# io-board-c-4.net
KiCad netlist of a schematic drawn in EAGLE
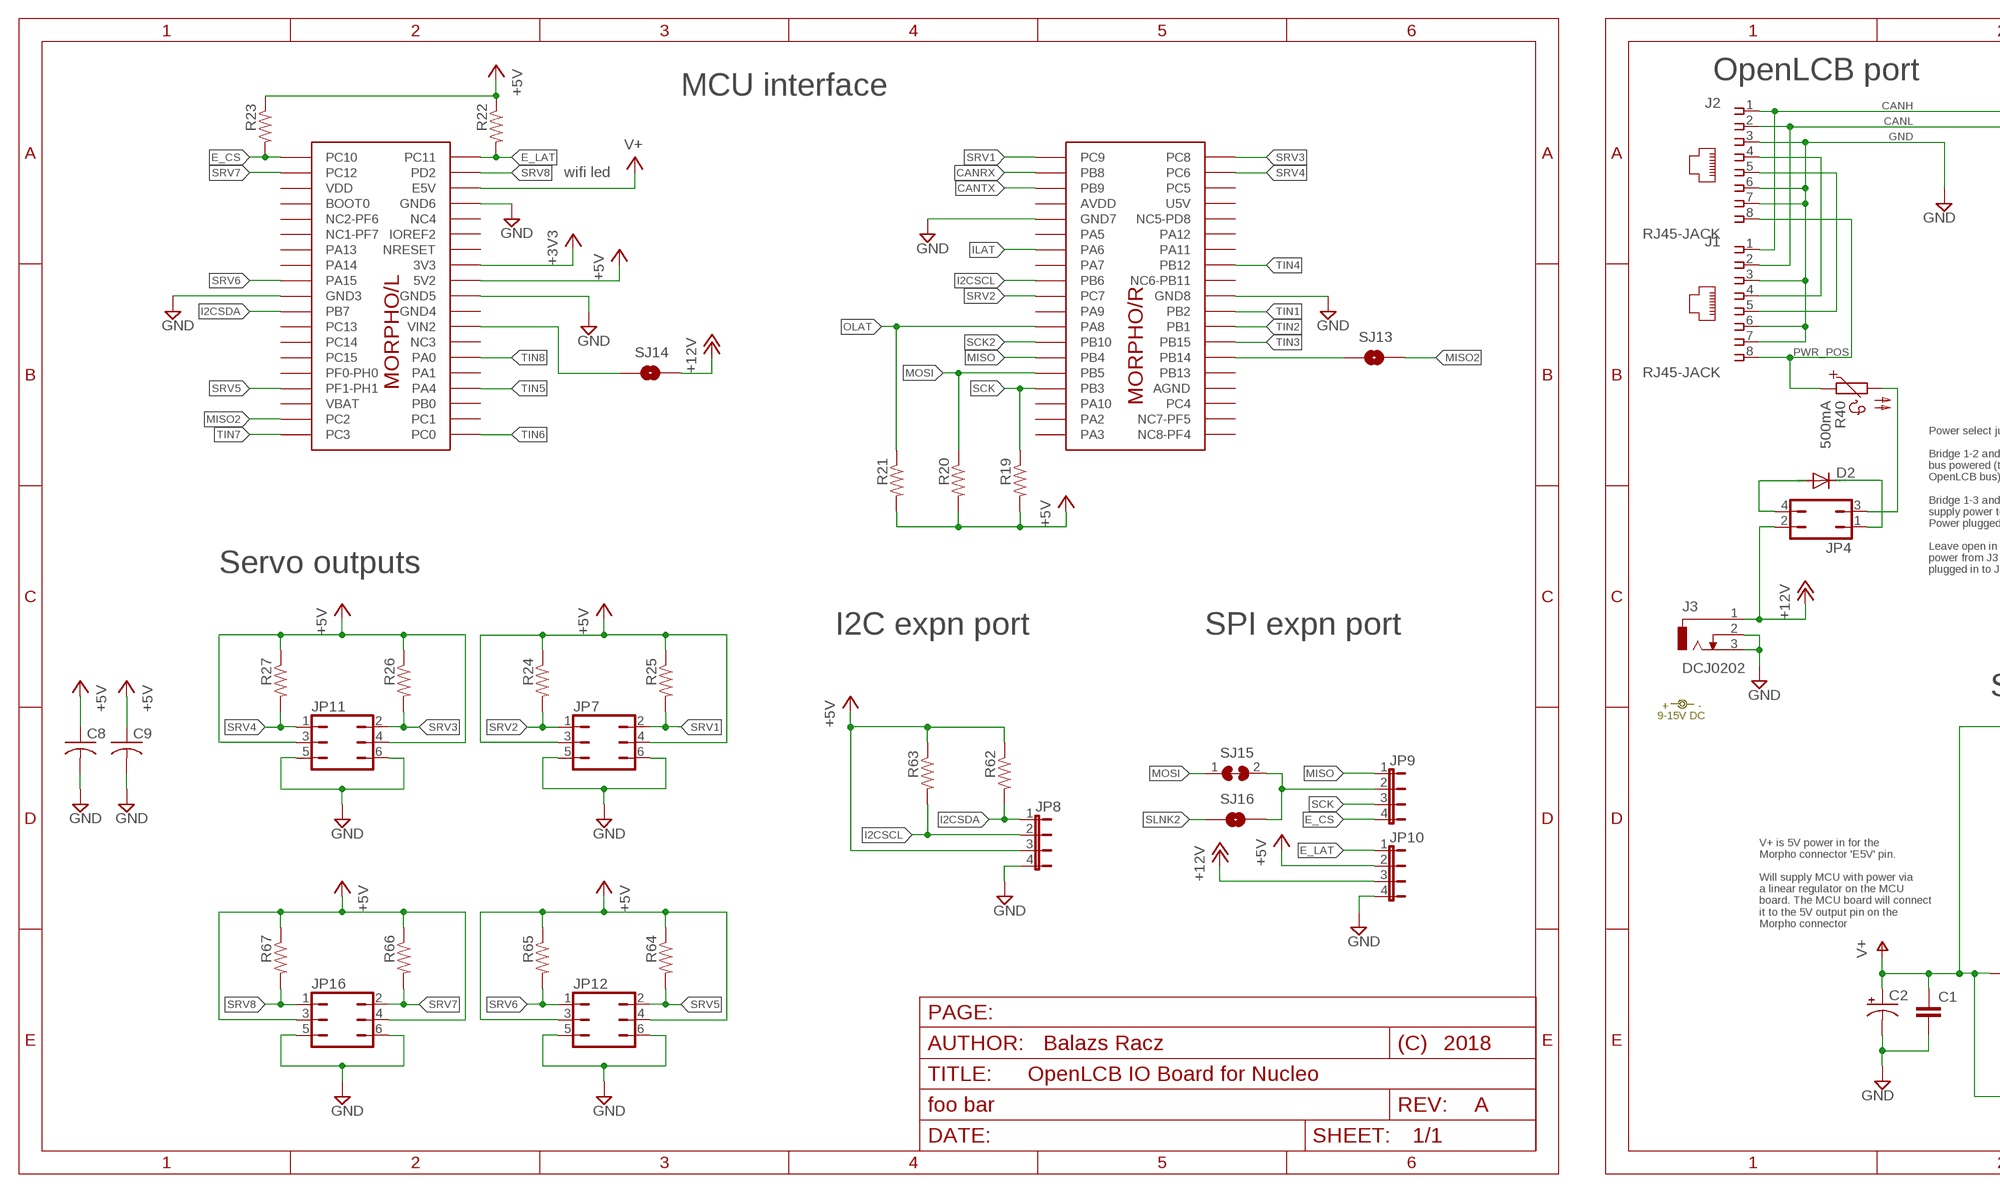
[diagram p0: schematic, sheet 1, part 1 of 3]
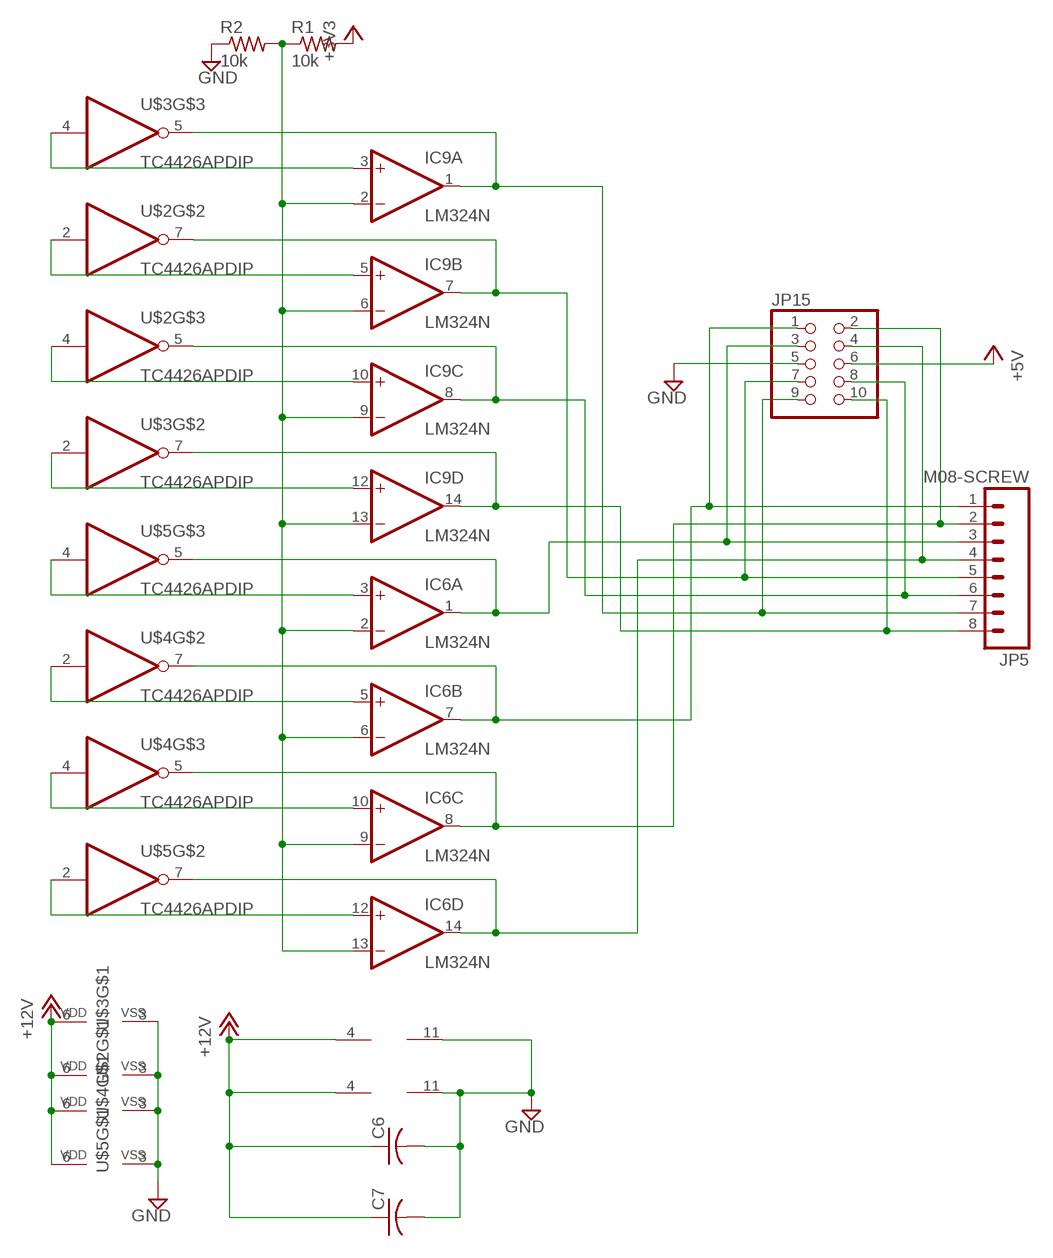
[diagram p1: schematic, sheet 1, part 2 of 3]
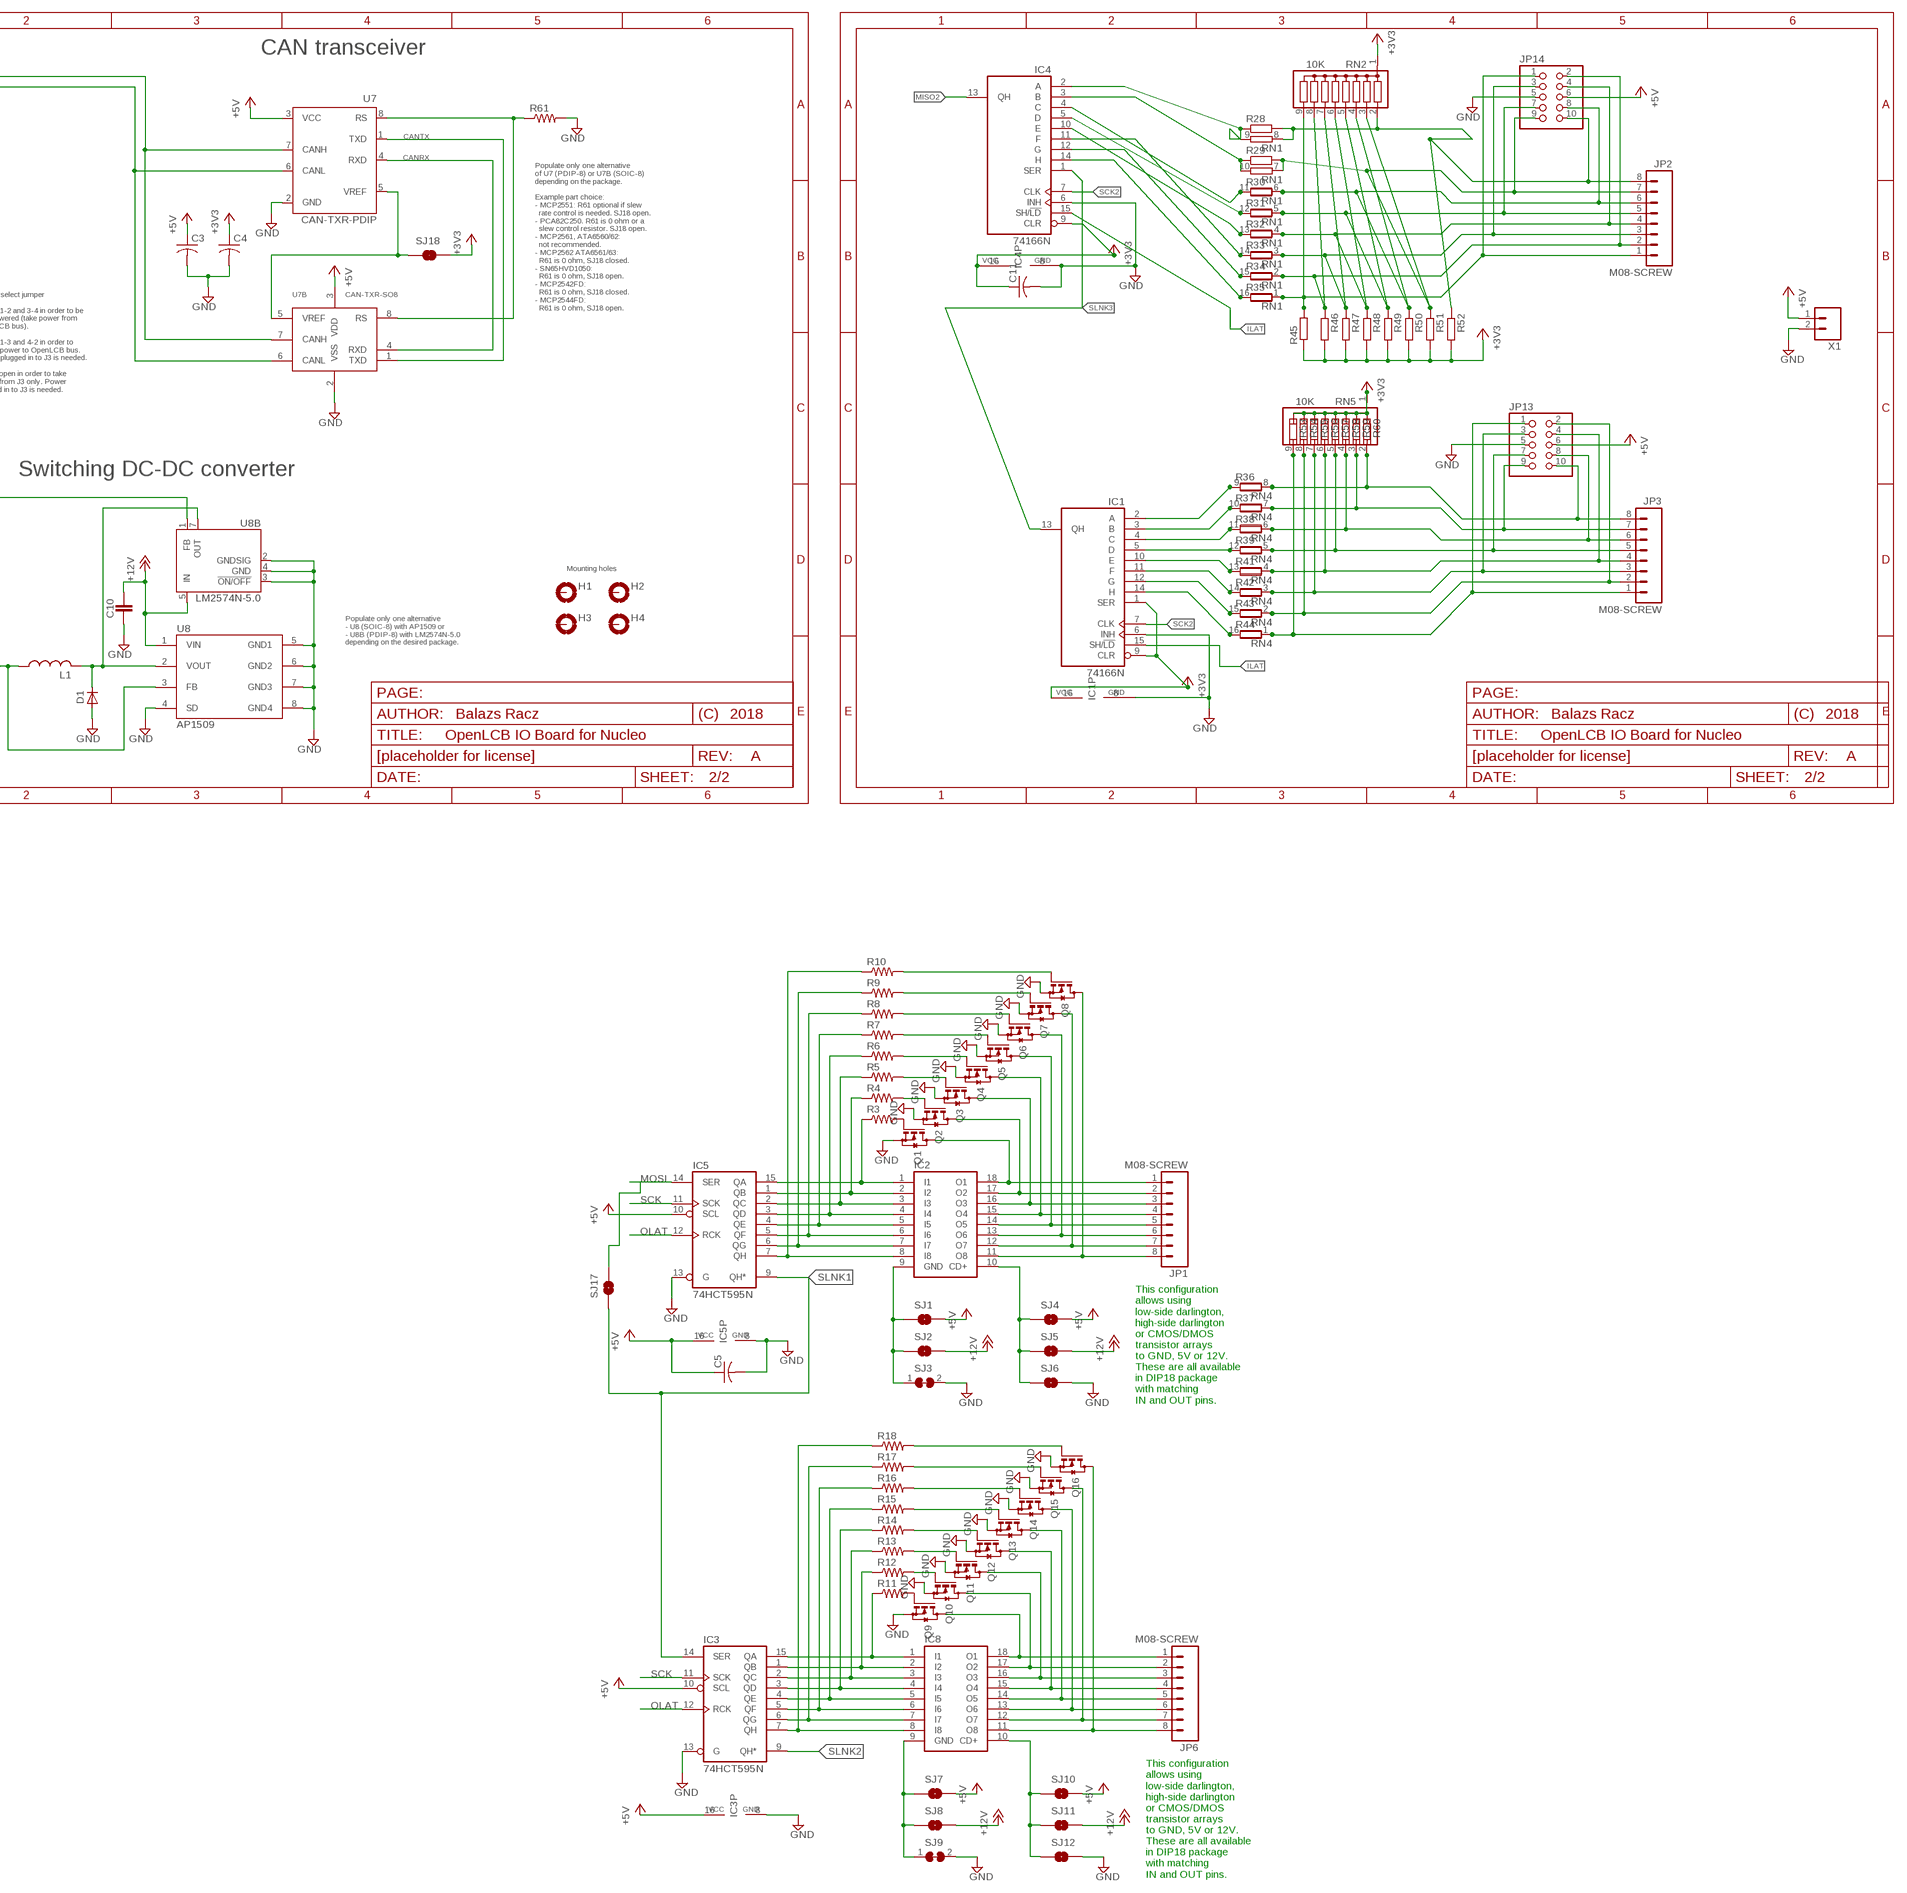
[diagram p2: schematic, sheet 1, part 3 of 3]

(export (version "E")
  (design (tool "Eeschema 10.0.6"))
  (components
    (comp (ref "+12V")
      (value "9-15V DC")
      (footprint "eagle-import:POWER_USAGE")
      (libsource (lib "eagle-import") (part "DOC-POWER_LABEL"))
    )
    (comp (ref "C1")
      (value "C-EUC1206")
      (footprint "eagle-import:C1206")
      (libsource (lib "eagle-import") (part "C-EUC1206"))
    )
    (comp (ref "C2")
      (value "CPOL-USE2.5-5")
      (footprint "eagle-import:E2,5-5")
      (libsource (lib "eagle-import") (part "CPOL-USE2.5-5"))
    )
    (comp (ref "C3")
      (value "C-USC0805")
      (footprint "eagle-import:C0805")
      (libsource (lib "eagle-import") (part "C-USC0805"))
    )
    (comp (ref "C4")
      (value "C-USC0805")
      (footprint "eagle-import:C0805")
      (libsource (lib "eagle-import") (part "C-USC0805"))
    )
    (comp (ref "C5")
      (value "C-USC0805")
      (footprint "eagle-import:C0805")
      (libsource (lib "eagle-import") (part "C-USC0805"))
    )
    (comp (ref "C6")
      (value "C-USC1206")
      (footprint "eagle-import:C1206")
      (libsource (lib "eagle-import") (part "C-USC1206"))
    )
    (comp (ref "C7")
      (value "C-USC1206")
      (footprint "eagle-import:C1206")
      (libsource (lib "eagle-import") (part "C-USC1206"))
    )
    (comp (ref "C8")
      (value "C-USC1206")
      (footprint "eagle-import:C1206")
      (libsource (lib "eagle-import") (part "C-USC1206"))
    )
    (comp (ref "C9")
      (value "C-USC1206")
      (footprint "eagle-import:C1206")
      (libsource (lib "eagle-import") (part "C-USC1206"))
    )
    (comp (ref "C10")
      (value "C-EUC1206")
      (footprint "eagle-import:C1206")
      (libsource (lib "eagle-import") (part "C-EUC1206"))
    )
    (comp (ref "C11")
      (value "C-USC0805")
      (footprint "eagle-import:C0805")
      (libsource (lib "eagle-import") (part "C-USC0805"))
    )
    (comp (ref "D1")
      (value "DIODE-DO41-7.6")
      (footprint "eagle-import:DO41-7.6")
      (libsource (lib "eagle-import") (part "DIODE-DO41-7.6"))
    )
    (comp (ref "D2")
      (value "DIODE-DO41-7.6")
      (footprint "eagle-import:DO41-7.6")
      (libsource (lib "eagle-import") (part "DIODE-DO41-7.6"))
    )
    (comp (ref "H1")
      (value "MOUNT-PAD-ROUND3.3")
      (footprint "eagle-import:3,3-PAD")
      (libsource (lib "eagle-import") (part "MOUNT-PAD-ROUND3.3"))
    )
    (comp (ref "H2")
      (value "MOUNT-PAD-ROUND3.3")
      (footprint "eagle-import:3,3-PAD")
      (libsource (lib "eagle-import") (part "MOUNT-PAD-ROUND3.3"))
    )
    (comp (ref "H3")
      (value "MOUNT-PAD-ROUND3.3")
      (footprint "eagle-import:3,3-PAD")
      (libsource (lib "eagle-import") (part "MOUNT-PAD-ROUND3.3"))
    )
    (comp (ref "H4")
      (value "MOUNT-PAD-ROUND3.3")
      (footprint "eagle-import:3,3-PAD")
      (libsource (lib "eagle-import") (part "MOUNT-PAD-ROUND3.3"))
    )
    (comp (ref "IC1")
      (value "74166N")
      (footprint "eagle-import:DIL16")
      (libsource (lib "eagle-import") (part "74166N"))
    )
    (comp (ref "IC2")
      (value "ULN2803A")
      (footprint "eagle-import:DIL18-THIN")
      (libsource (lib "eagle-import") (part "ULN2803A"))
    )
    (comp (ref "IC3")
      (value "74HCT595N")
      (footprint "eagle-import:DIL16")
      (libsource (lib "eagle-import") (part "74595NHCT"))
    )
    (comp (ref "IC4")
      (value "74166N")
      (footprint "eagle-import:DIL16")
      (libsource (lib "eagle-import") (part "74166N"))
    )
    (comp (ref "IC5")
      (value "74HCT595N")
      (footprint "eagle-import:DIL16")
      (libsource (lib "eagle-import") (part "74595NHCT"))
    )
    (comp (ref "IC6")
      (value "LM324N")
      (footprint "eagle-import:DIL14")
      (libsource (lib "eagle-import") (part "LM324N"))
    )
    (comp (ref "IC8")
      (value "ULN2803A")
      (footprint "eagle-import:DIL18-THIN")
      (libsource (lib "eagle-import") (part "ULN2803A"))
    )
    (comp (ref "IC9")
      (value "LM324N")
      (footprint "eagle-import:DIL14")
      (libsource (lib "eagle-import") (part "LM324N"))
    )
    (comp (ref "J1")
      (value "RJ45-JACK")
      (footprint "eagle-import:RJ45-PULSE-E5J88")
      (libsource (lib "eagle-import") (part "RJ45-JACKRJ45-PULSE-E5J00"))
    )
    (comp (ref "J2")
      (value "RJ45-JACK")
      (footprint "eagle-import:RJ45-PULSE-E5J88")
      (libsource (lib "eagle-import") (part "RJ45-JACKRJ45-PULSE-E5J00"))
    )
    (comp (ref "J3")
      (value "DCJ0202")
      (footprint "eagle-import:DCJ0202")
      (libsource (lib "eagle-import") (part "DCJ0202"))
    )
    (comp (ref "JP1")
      (value "M08-SCREW")
      (footprint "eagle-import:1X08_TERMINAL")
      (libsource (lib "eagle-import") (part "M08-SCREW"))
    )
    (comp (ref "JP2")
      (value "M08-SCREW")
      (footprint "eagle-import:1X08_TERMINAL")
      (libsource (lib "eagle-import") (part "M08-SCREW"))
    )
    (comp (ref "JP3")
      (value "M08-SCREW")
      (footprint "eagle-import:1X08_TERMINAL")
      (libsource (lib "eagle-import") (part "M08-SCREW"))
    )
    (comp (ref "JP4")
      (value "JP2Q")
      (footprint "eagle-import:JP2Q")
      (libsource (lib "eagle-import") (part "JP2Q"))
    )
    (comp (ref "JP5")
      (value "M08-SCREW")
      (footprint "eagle-import:1X08_TERMINAL")
      (libsource (lib "eagle-import") (part "M08-SCREW"))
    )
    (comp (ref "JP6")
      (value "M08-SCREW")
      (footprint "eagle-import:1X08_TERMINAL")
      (libsource (lib "eagle-import") (part "M08-SCREW"))
    )
    (comp (ref "JP7")
      (value "JP3Q")
      (footprint "eagle-import:JP3Q")
      (libsource (lib "eagle-import") (part "JP3Q"))
    )
    (comp (ref "JP8")
      (value "JP4-FLAT")
      (footprint "eagle-import:JP4F")
      (libsource (lib "eagle-import") (part "JP4-FLAT"))
    )
    (comp (ref "JP9")
      (value "JP4-FLAT")
      (footprint "eagle-import:JP4F")
      (libsource (lib "eagle-import") (part "JP4-FLAT"))
    )
    (comp (ref "JP10")
      (value "JP4-FLAT")
      (footprint "eagle-import:JP4F")
      (libsource (lib "eagle-import") (part "JP4-FLAT"))
    )
    (comp (ref "JP11")
      (value "JP3Q")
      (footprint "eagle-import:JP3Q")
      (libsource (lib "eagle-import") (part "JP3Q"))
    )
    (comp (ref "JP12")
      (value "JP3Q")
      (footprint "eagle-import:JP3Q")
      (libsource (lib "eagle-import") (part "JP3Q"))
    )
    (comp (ref "JP13")
      (value "PINHD-2X5CN")
      (footprint "eagle-import:CON10M")
      (libsource (lib "eagle-import") (part "PINHD-2X5CN"))
    )
    (comp (ref "JP14")
      (value "PINHD-2X5CN")
      (footprint "eagle-import:CON10M")
      (libsource (lib "eagle-import") (part "PINHD-2X5CN"))
    )
    (comp (ref "JP15")
      (value "PINHD-2X5CN")
      (footprint "eagle-import:CON10M")
      (libsource (lib "eagle-import") (part "PINHD-2X5CN"))
    )
    (comp (ref "JP16")
      (value "JP3Q")
      (footprint "eagle-import:JP3Q")
      (libsource (lib "eagle-import") (part "JP3Q"))
    )
    (comp (ref "L1")
      (value "L-US")
      (footprint "eagle-import:L5-8,5")
      (libsource (lib "eagle-import") (part "L-US"))
    )
    (comp (ref "Q1")
      (value "BSS123")
      (footprint "eagle-import:SOT23")
      (libsource (lib "eagle-import") (part "BSS123"))
    )
    (comp (ref "Q2")
      (value "BSS123")
      (footprint "eagle-import:SOT23")
      (libsource (lib "eagle-import") (part "BSS123"))
    )
    (comp (ref "Q3")
      (value "BSS123")
      (footprint "eagle-import:SOT23")
      (libsource (lib "eagle-import") (part "BSS123"))
    )
    (comp (ref "Q4")
      (value "BSS123")
      (footprint "eagle-import:SOT23")
      (libsource (lib "eagle-import") (part "BSS123"))
    )
    (comp (ref "Q5")
      (value "BSS123")
      (footprint "eagle-import:SOT23")
      (libsource (lib "eagle-import") (part "BSS123"))
    )
    (comp (ref "Q6")
      (value "BSS123")
      (footprint "eagle-import:SOT23")
      (libsource (lib "eagle-import") (part "BSS123"))
    )
    (comp (ref "Q7")
      (value "BSS123")
      (footprint "eagle-import:SOT23")
      (libsource (lib "eagle-import") (part "BSS123"))
    )
    (comp (ref "Q8")
      (value "BSS123")
      (footprint "eagle-import:SOT23")
      (libsource (lib "eagle-import") (part "BSS123"))
    )
    (comp (ref "Q9")
      (value "BSS123")
      (footprint "eagle-import:SOT23")
      (libsource (lib "eagle-import") (part "BSS123"))
    )
    (comp (ref "Q10")
      (value "BSS123")
      (footprint "eagle-import:SOT23")
      (libsource (lib "eagle-import") (part "BSS123"))
    )
    (comp (ref "Q11")
      (value "BSS123")
      (footprint "eagle-import:SOT23")
      (libsource (lib "eagle-import") (part "BSS123"))
    )
    (comp (ref "Q12")
      (value "BSS123")
      (footprint "eagle-import:SOT23")
      (libsource (lib "eagle-import") (part "BSS123"))
    )
    (comp (ref "Q13")
      (value "BSS123")
      (footprint "eagle-import:SOT23")
      (libsource (lib "eagle-import") (part "BSS123"))
    )
    (comp (ref "Q14")
      (value "BSS123")
      (footprint "eagle-import:SOT23")
      (libsource (lib "eagle-import") (part "BSS123"))
    )
    (comp (ref "Q15")
      (value "BSS123")
      (footprint "eagle-import:SOT23")
      (libsource (lib "eagle-import") (part "BSS123"))
    )
    (comp (ref "Q16")
      (value "BSS123")
      (footprint "eagle-import:SOT23")
      (libsource (lib "eagle-import") (part "BSS123"))
    )
    (comp (ref "R1")
      (value "10k")
      (footprint "eagle-import:R0805")
      (libsource (lib "eagle-import") (part "R-US_R0805"))
    )
    (comp (ref "R2")
      (value "10k")
      (footprint "eagle-import:R0805")
      (libsource (lib "eagle-import") (part "R-US_R0805"))
    )
    (comp (ref "R3")
      (value "R-US_R0603")
      (footprint "eagle-import:R0603")
      (libsource (lib "eagle-import") (part "R-US_R0603"))
    )
    (comp (ref "R4")
      (value "R-US_R0603")
      (footprint "eagle-import:R0603")
      (libsource (lib "eagle-import") (part "R-US_R0603"))
    )
    (comp (ref "R5")
      (value "R-US_R0603")
      (footprint "eagle-import:R0603")
      (libsource (lib "eagle-import") (part "R-US_R0603"))
    )
    (comp (ref "R6")
      (value "R-US_R0603")
      (footprint "eagle-import:R0603")
      (libsource (lib "eagle-import") (part "R-US_R0603"))
    )
    (comp (ref "R7")
      (value "R-US_R0603")
      (footprint "eagle-import:R0603")
      (libsource (lib "eagle-import") (part "R-US_R0603"))
    )
    (comp (ref "R8")
      (value "R-US_R0603")
      (footprint "eagle-import:R0603")
      (libsource (lib "eagle-import") (part "R-US_R0603"))
    )
    (comp (ref "R9")
      (value "R-US_R0603")
      (footprint "eagle-import:R0603")
      (libsource (lib "eagle-import") (part "R-US_R0603"))
    )
    (comp (ref "R10")
      (value "R-US_R0603")
      (footprint "eagle-import:R0603")
      (libsource (lib "eagle-import") (part "R-US_R0603"))
    )
    (comp (ref "R11")
      (value "R-US_R0603")
      (footprint "eagle-import:R0603")
      (libsource (lib "eagle-import") (part "R-US_R0603"))
    )
    (comp (ref "R12")
      (value "R-US_R0603")
      (footprint "eagle-import:R0603")
      (libsource (lib "eagle-import") (part "R-US_R0603"))
    )
    (comp (ref "R13")
      (value "R-US_R0603")
      (footprint "eagle-import:R0603")
      (libsource (lib "eagle-import") (part "R-US_R0603"))
    )
    (comp (ref "R14")
      (value "R-US_R0603")
      (footprint "eagle-import:R0603")
      (libsource (lib "eagle-import") (part "R-US_R0603"))
    )
    (comp (ref "R15")
      (value "R-US_R0603")
      (footprint "eagle-import:R0603")
      (libsource (lib "eagle-import") (part "R-US_R0603"))
    )
    (comp (ref "R16")
      (value "R-US_R0603")
      (footprint "eagle-import:R0603")
      (libsource (lib "eagle-import") (part "R-US_R0603"))
    )
    (comp (ref "R17")
      (value "R-US_R0603")
      (footprint "eagle-import:R0603")
      (libsource (lib "eagle-import") (part "R-US_R0603"))
    )
    (comp (ref "R18")
      (value "R-US_R0603")
      (footprint "eagle-import:R0603")
      (libsource (lib "eagle-import") (part "R-US_R0603"))
    )
    (comp (ref "R19")
      (value "R-US_R0805")
      (footprint "eagle-import:R0805")
      (libsource (lib "eagle-import") (part "rcl_334_R-US_R0805"))
    )
    (comp (ref "R20")
      (value "R-US_R0805")
      (footprint "eagle-import:R0805")
      (libsource (lib "eagle-import") (part "rcl_334_R-US_R0805"))
    )
    (comp (ref "R21")
      (value "R-US_R0805")
      (footprint "eagle-import:R0805")
      (libsource (lib "eagle-import") (part "rcl_334_R-US_R0805"))
    )
    (comp (ref "R22")
      (value "R-US_R0805")
      (footprint "eagle-import:R0805")
      (libsource (lib "eagle-import") (part "rcl_334_R-US_R0805"))
    )
    (comp (ref "R23")
      (value "R-US_R0805")
      (footprint "eagle-import:R0805")
      (libsource (lib "eagle-import") (part "rcl_334_R-US_R0805"))
    )
    (comp (ref "R24")
      (value "R-US_R0805")
      (footprint "eagle-import:R0805")
      (libsource (lib "eagle-import") (part "rcl_334_R-US_R0805"))
    )
    (comp (ref "R25")
      (value "R-US_R0805")
      (footprint "eagle-import:R0805")
      (libsource (lib "eagle-import") (part "rcl_334_R-US_R0805"))
    )
    (comp (ref "R26")
      (value "R-US_R0805")
      (footprint "eagle-import:R0805")
      (libsource (lib "eagle-import") (part "rcl_334_R-US_R0805"))
    )
    (comp (ref "R27")
      (value "R-US_R0805")
      (footprint "eagle-import:R0805")
      (libsource (lib "eagle-import") (part "rcl_334_R-US_R0805"))
    )
    (comp (ref "R28")
      (value "R-EU_R0603")
      (footprint "eagle-import:R0603")
      (libsource (lib "eagle-import") (part "R-EU_R0603"))
    )
    (comp (ref "R29")
      (value "R-EU_R0603")
      (footprint "eagle-import:R0603")
      (libsource (lib "eagle-import") (part "R-EU_R0603"))
    )
    (comp (ref "R30")
      (value "R-EU_R0603")
      (footprint "eagle-import:R0603")
      (libsource (lib "eagle-import") (part "R-EU_R0603"))
    )
    (comp (ref "R31")
      (value "R-EU_R0603")
      (footprint "eagle-import:R0603")
      (libsource (lib "eagle-import") (part "R-EU_R0603"))
    )
    (comp (ref "R32")
      (value "R-EU_R0603")
      (footprint "eagle-import:R0603")
      (libsource (lib "eagle-import") (part "R-EU_R0603"))
    )
    (comp (ref "R33")
      (value "R-EU_R0603")
      (footprint "eagle-import:R0603")
      (libsource (lib "eagle-import") (part "R-EU_R0603"))
    )
    (comp (ref "R34")
      (value "R-EU_R0603")
      (footprint "eagle-import:R0603")
      (libsource (lib "eagle-import") (part "R-EU_R0603"))
    )
    (comp (ref "R35")
      (value "R-EU_R0603")
      (footprint "eagle-import:R0603")
      (libsource (lib "eagle-import") (part "R-EU_R0603"))
    )
    (comp (ref "R36")
      (value "R-EU_R0603")
      (footprint "eagle-import:R0603")
      (libsource (lib "eagle-import") (part "R-EU_R0603"))
    )
    (comp (ref "R37")
      (value "R-EU_R0603")
      (footprint "eagle-import:R0603")
      (libsource (lib "eagle-import") (part "R-EU_R0603"))
    )
    (comp (ref "R38")
      (value "R-EU_R0603")
      (footprint "eagle-import:R0603")
      (libsource (lib "eagle-import") (part "R-EU_R0603"))
    )
    (comp (ref "R39")
      (value "R-EU_R0603")
      (footprint "eagle-import:R0603")
      (libsource (lib "eagle-import") (part "R-EU_R0603"))
    )
    (comp (ref "R40")
      (value "500mA")
      (footprint "eagle-import:PTC1812")
      (libsource (lib "eagle-import") (part "PTC_1812"))
    )
    (comp (ref "R41")
      (value "R-EU_R0603")
      (footprint "eagle-import:R0603")
      (libsource (lib "eagle-import") (part "R-EU_R0603"))
    )
    (comp (ref "R42")
      (value "R-EU_R0603")
      (footprint "eagle-import:R0603")
      (libsource (lib "eagle-import") (part "R-EU_R0603"))
    )
    (comp (ref "R43")
      (value "R-EU_R0603")
      (footprint "eagle-import:R0603")
      (libsource (lib "eagle-import") (part "R-EU_R0603"))
    )
    (comp (ref "R44")
      (value "R-EU_R0603")
      (footprint "eagle-import:R0603")
      (libsource (lib "eagle-import") (part "R-EU_R0603"))
    )
    (comp (ref "R45")
      (value "R-EU_R0603")
      (footprint "eagle-import:R0603")
      (libsource (lib "eagle-import") (part "R-EU_R0603"))
    )
    (comp (ref "R46")
      (value "R-EU_R0603")
      (footprint "eagle-import:R0603")
      (libsource (lib "eagle-import") (part "R-EU_R0603"))
    )
    (comp (ref "R47")
      (value "R-EU_R0603")
      (footprint "eagle-import:R0603")
      (libsource (lib "eagle-import") (part "R-EU_R0603"))
    )
    (comp (ref "R48")
      (value "R-EU_R0603")
      (footprint "eagle-import:R0603")
      (libsource (lib "eagle-import") (part "R-EU_R0603"))
    )
    (comp (ref "R49")
      (value "R-EU_R0603")
      (footprint "eagle-import:R0603")
      (libsource (lib "eagle-import") (part "R-EU_R0603"))
    )
    (comp (ref "R50")
      (value "R-EU_R0603")
      (footprint "eagle-import:R0603")
      (libsource (lib "eagle-import") (part "R-EU_R0603"))
    )
    (comp (ref "R51")
      (value "R-EU_R0603")
      (footprint "eagle-import:R0603")
      (libsource (lib "eagle-import") (part "R-EU_R0603"))
    )
    (comp (ref "R52")
      (value "R-EU_R0603")
      (footprint "eagle-import:R0603")
      (libsource (lib "eagle-import") (part "R-EU_R0603"))
    )
    (comp (ref "R53")
      (value "R-EU_R0603")
      (footprint "eagle-import:R0603")
      (libsource (lib "eagle-import") (part "R-EU_R0603"))
    )
    (comp (ref "R54")
      (value "R-EU_R0603")
      (footprint "eagle-import:R0603")
      (libsource (lib "eagle-import") (part "R-EU_R0603"))
    )
    (comp (ref "R55")
      (value "R-EU_R0603")
      (footprint "eagle-import:R0603")
      (libsource (lib "eagle-import") (part "R-EU_R0603"))
    )
    (comp (ref "R56")
      (value "R-EU_R0603")
      (footprint "eagle-import:R0603")
      (libsource (lib "eagle-import") (part "R-EU_R0603"))
    )
    (comp (ref "R57")
      (value "R-EU_R0603")
      (footprint "eagle-import:R0603")
      (libsource (lib "eagle-import") (part "R-EU_R0603"))
    )
    (comp (ref "R58")
      (value "R-EU_R0603")
      (footprint "eagle-import:R0603")
      (libsource (lib "eagle-import") (part "R-EU_R0603"))
    )
    (comp (ref "R59")
      (value "R-EU_R0603")
      (footprint "eagle-import:R0603")
      (libsource (lib "eagle-import") (part "R-EU_R0603"))
    )
    (comp (ref "R60")
      (value "R-EU_R0603")
      (footprint "eagle-import:R0603")
      (libsource (lib "eagle-import") (part "R-EU_R0603"))
    )
    (comp (ref "R61")
      (value "R-US_R0805")
      (footprint "eagle-import:R0805")
      (libsource (lib "eagle-import") (part "rcl_334_R-US_R0805"))
    )
    (comp (ref "R62")
      (value "R-US_R0805")
      (footprint "eagle-import:R0805")
      (libsource (lib "eagle-import") (part "rcl_334_R-US_R0805"))
    )
    (comp (ref "R63")
      (value "R-US_R0805")
      (footprint "eagle-import:R0805")
      (libsource (lib "eagle-import") (part "rcl_334_R-US_R0805"))
    )
    (comp (ref "R64")
      (value "R-US_R0805")
      (footprint "eagle-import:R0805")
      (libsource (lib "eagle-import") (part "rcl_334_R-US_R0805"))
    )
    (comp (ref "R65")
      (value "R-US_R0805")
      (footprint "eagle-import:R0805")
      (libsource (lib "eagle-import") (part "rcl_334_R-US_R0805"))
    )
    (comp (ref "R66")
      (value "R-US_R0805")
      (footprint "eagle-import:R0805")
      (libsource (lib "eagle-import") (part "rcl_334_R-US_R0805"))
    )
    (comp (ref "R67")
      (value "R-US_R0805")
      (footprint "eagle-import:R0805")
      (libsource (lib "eagle-import") (part "rcl_334_R-US_R0805"))
    )
    (comp (ref "RN1")
      (value "8R-P")
      (footprint "eagle-import:DIL16")
      (libsource (lib "eagle-import") (part "8R-P"))
    )
    (comp (ref "RN2")
      (value "10K")
      (footprint "eagle-import:SIL9")
      (libsource (lib "eagle-import") (part "G08R"))
    )
    (comp (ref "RN4")
      (value "8R-P")
      (footprint "eagle-import:DIL16")
      (libsource (lib "eagle-import") (part "8R-P"))
    )
    (comp (ref "RN5")
      (value "10K")
      (footprint "eagle-import:SIL9")
      (libsource (lib "eagle-import") (part "G08R"))
    )
    (comp (ref "SJ1")
      (value "SJRND2")
      (footprint "eagle-import:SJ_RND2")
      (libsource (lib "eagle-import") (part "SJRND2"))
    )
    (comp (ref "SJ2")
      (value "SJRND2")
      (footprint "eagle-import:SJ_RND2")
      (libsource (lib "eagle-import") (part "SJRND2"))
    )
    (comp (ref "SJ3")
      (value "SJ-C")
      (footprint "eagle-import:SJW-C")
      (libsource (lib "eagle-import") (part "SJ-C"))
    )
    (comp (ref "SJ4")
      (value "SJRND2")
      (footprint "eagle-import:SJ_RND2")
      (libsource (lib "eagle-import") (part "SJRND2"))
    )
    (comp (ref "SJ5")
      (value "SJRND2")
      (footprint "eagle-import:SJ_RND2")
      (libsource (lib "eagle-import") (part "SJRND2"))
    )
    (comp (ref "SJ6")
      (value "SJRND2")
      (footprint "eagle-import:SJ_RND2")
      (libsource (lib "eagle-import") (part "SJRND2"))
    )
    (comp (ref "SJ7")
      (value "SJRND2")
      (footprint "eagle-import:SJ_RND2")
      (libsource (lib "eagle-import") (part "SJRND2"))
    )
    (comp (ref "SJ8")
      (value "SJRND2")
      (footprint "eagle-import:SJ_RND2")
      (libsource (lib "eagle-import") (part "SJRND2"))
    )
    (comp (ref "SJ9")
      (value "SJ-C")
      (footprint "eagle-import:SJW-C")
      (libsource (lib "eagle-import") (part "SJ-C"))
    )
    (comp (ref "SJ10")
      (value "SJRND2")
      (footprint "eagle-import:SJ_RND2")
      (libsource (lib "eagle-import") (part "SJRND2"))
    )
    (comp (ref "SJ11")
      (value "SJRND2")
      (footprint "eagle-import:SJ_RND2")
      (libsource (lib "eagle-import") (part "SJRND2"))
    )
    (comp (ref "SJ12")
      (value "SJRND2")
      (footprint "eagle-import:SJ_RND2")
      (libsource (lib "eagle-import") (part "SJRND2"))
    )
    (comp (ref "SJ13")
      (value "SJRND2")
      (footprint "eagle-import:SJ_RND2")
      (libsource (lib "eagle-import") (part "SJRND2"))
    )
    (comp (ref "SJ14")
      (value "SJRND2")
      (footprint "eagle-import:SJ_RND2")
      (libsource (lib "eagle-import") (part "SJRND2"))
    )
    (comp (ref "SJ15")
      (value "SJ-C")
      (footprint "eagle-import:SJW-C")
      (libsource (lib "eagle-import") (part "SJ-C"))
    )
    (comp (ref "SJ16")
      (value "SJRND2")
      (footprint "eagle-import:SJ_RND2")
      (libsource (lib "eagle-import") (part "SJRND2"))
    )
    (comp (ref "SJ17")
      (value "SJRND2")
      (footprint "eagle-import:SJ_RND2")
      (libsource (lib "eagle-import") (part "SJRND2"))
    )
    (comp (ref "SJ18")
      (value "SJRND2")
      (footprint "eagle-import:SJ_RND2")
      (libsource (lib "eagle-import") (part "SJRND2"))
    )
    (comp (ref "U$1")
      (value "NUCLEO_64_GENERIC")
      (footprint "eagle-import:NUCLEO_BRD_BASE64")
      (libsource (lib "eagle-import") (part "NUCLEO_64_GENERIC"))
    )
    (comp (ref "U$2")
      (value "TC4426APDIP")
      (footprint "eagle-import:DIL08-LONG")
      (libsource (lib "eagle-import") (part "TC4426APDIP"))
    )
    (comp (ref "U$3")
      (value "TC4426APDIP")
      (footprint "eagle-import:DIL08-LONG")
      (libsource (lib "eagle-import") (part "TC4426APDIP"))
    )
    (comp (ref "U$4")
      (value "TC4426APDIP")
      (footprint "eagle-import:DIL08-LONG")
      (libsource (lib "eagle-import") (part "TC4426APDIP"))
    )
    (comp (ref "U$5")
      (value "TC4426APDIP")
      (footprint "eagle-import:DIL08-LONG")
      (libsource (lib "eagle-import") (part "TC4426APDIP"))
    )
    (comp (ref "U7")
      (value "CAN-TXR-PDIP")
      (footprint "eagle-import:DIL08")
      (libsource (lib "eagle-import") (part "PCA82C250"))
    )
    (comp (ref "U7B")
      (value "CAN-TXR-SO8")
      (footprint "eagle-import:SO-08")
      (libsource (lib "eagle-import") (part "MCP2551-SN"))
    )
    (comp (ref "U8")
      (value "AP1509")
      (footprint "eagle-import:SO-08")
      (libsource (lib "eagle-import") (part "AP1509"))
    )
    (comp (ref "U8B")
      (value "LM2574N-5.0")
      (footprint "eagle-import:DIL08")
      (libsource (lib "eagle-import") (part "LM2574?-N5.0"))
    )
    (comp (ref "X1")
      (value "CONNECTOR-M023.5MM-LOCK")
      (footprint "eagle-import:SCREWTERMINAL-3.5MM-2_LOCK")
      (libsource (lib "eagle-import") (part "CONNECTOR-M023.5MM-LOCK"))
    )
  )
  (nets
    (net (code "1") (name "+3V3") (class "Default")
      (node (ref "C11") (pin "1") (pinfunction "1_1") (pintype "passive"))
      (node (ref "C4") (pin "1") (pinfunction "1_1") (pintype "passive"))
      (node (ref "IC1") (pin "1") (pinfunction "SER_1") (pintype "input"))
      (node (ref "IC1") (pin "16") (pinfunction "VCC_16") (pintype "power_in"))
      (node (ref "IC1") (pin "9") (pinfunction "CLR_9") (pintype "input"))
      (node (ref "IC4") (pin "16") (pinfunction "VCC_16") (pintype "power_in"))
      (node (ref "IC4") (pin "9") (pinfunction "CLR_9") (pintype "input"))
      (node (ref "R1") (pin "2") (pinfunction "2_2") (pintype "passive"))
      (node (ref "R45") (pin "1") (pinfunction "1_1") (pintype "passive"))
      (node (ref "R46") (pin "2") (pinfunction "2_2") (pintype "passive"))
      (node (ref "R47") (pin "2") (pinfunction "2_2") (pintype "passive"))
      (node (ref "R48") (pin "2") (pinfunction "2_2") (pintype "passive"))
      (node (ref "R49") (pin "2") (pinfunction "2_2") (pintype "passive"))
      (node (ref "R50") (pin "2") (pinfunction "2_2") (pintype "passive"))
      (node (ref "R51") (pin "2") (pinfunction "2_2") (pintype "passive"))
      (node (ref "R52") (pin "2") (pinfunction "2_2") (pintype "passive"))
      (node (ref "R53") (pin "1") (pinfunction "1_1") (pintype "passive"))
      (node (ref "R54") (pin "1") (pinfunction "1_1") (pintype "passive"))
      (node (ref "R55") (pin "1") (pinfunction "1_1") (pintype "passive"))
      (node (ref "R56") (pin "1") (pinfunction "1_1") (pintype "passive"))
      (node (ref "R57") (pin "1") (pinfunction "1_1") (pintype "passive"))
      (node (ref "R58") (pin "1") (pinfunction "1_1") (pintype "passive"))
      (node (ref "R59") (pin "1") (pinfunction "1_1") (pintype "passive"))
      (node (ref "R60") (pin "1") (pinfunction "1_1") (pintype "passive"))
      (node (ref "RN2") (pin "1") (pinfunction "1_1") (pintype "passive"))
      (node (ref "RN5") (pin "1") (pinfunction "1_1") (pintype "passive"))
      (node (ref "SJ18") (pin "P$1") (pinfunction "1_P$1") (pintype "passive"))
      (node (ref "U$1") (pin "3V3") (pinfunction "3V3_3V3") (pintype "power_in"))
    )
    (net (code "2") (name "+5V") (class "Default")
      (node (ref "C3") (pin "1") (pinfunction "1_1") (pintype "passive"))
      (node (ref "C5") (pin "1") (pinfunction "1_1") (pintype "passive"))
      (node (ref "C8") (pin "1") (pinfunction "1_1") (pintype "passive"))
      (node (ref "C9") (pin "1") (pinfunction "1_1") (pintype "passive"))
      (node (ref "IC3") (pin "10") (pinfunction "SCL_10") (pintype "input"))
      (node (ref "IC3") (pin "16") (pinfunction "VCC_16") (pintype "power_in"))
      (node (ref "IC5") (pin "10") (pinfunction "SCL_10") (pintype "input"))
      (node (ref "IC5") (pin "16") (pinfunction "VCC_16") (pintype "power_in"))
      (node (ref "JP10") (pin "2") (pinfunction "2_2") (pintype "passive"))
      (node (ref "JP11") (pin "3") (pinfunction "3_3") (pintype "passive"))
      (node (ref "JP11") (pin "4") (pinfunction "4_4") (pintype "passive"))
      (node (ref "JP12") (pin "3") (pinfunction "3_3") (pintype "passive"))
      (node (ref "JP12") (pin "4") (pinfunction "4_4") (pintype "passive"))
      (node (ref "JP13") (pin "6") (pinfunction "6_6") (pintype "passive"))
      (node (ref "JP14") (pin "6") (pinfunction "6_6") (pintype "passive"))
      (node (ref "JP15") (pin "6") (pinfunction "6_6") (pintype "passive"))
      (node (ref "JP16") (pin "3") (pinfunction "3_3") (pintype "passive"))
      (node (ref "JP16") (pin "4") (pinfunction "4_4") (pintype "passive"))
      (node (ref "JP7") (pin "3") (pinfunction "3_3") (pintype "passive"))
      (node (ref "JP7") (pin "4") (pinfunction "4_4") (pintype "passive"))
      (node (ref "JP8") (pin "3") (pinfunction "3_3") (pintype "passive"))
      (node (ref "R19") (pin "2") (pinfunction "2_2") (pintype "passive"))
      (node (ref "R20") (pin "2") (pinfunction "2_2") (pintype "passive"))
      (node (ref "R21") (pin "2") (pinfunction "2_2") (pintype "passive"))
      (node (ref "R22") (pin "1") (pinfunction "1_1") (pintype "passive"))
      (node (ref "R23") (pin "1") (pinfunction "1_1") (pintype "passive"))
      (node (ref "R24") (pin "1") (pinfunction "1_1") (pintype "passive"))
      (node (ref "R25") (pin "1") (pinfunction "1_1") (pintype "passive"))
      (node (ref "R26") (pin "1") (pinfunction "1_1") (pintype "passive"))
      (node (ref "R27") (pin "1") (pinfunction "1_1") (pintype "passive"))
      (node (ref "R62") (pin "1") (pinfunction "1_1") (pintype "passive"))
      (node (ref "R63") (pin "1") (pinfunction "1_1") (pintype "passive"))
      (node (ref "R64") (pin "1") (pinfunction "1_1") (pintype "passive"))
      (node (ref "R65") (pin "1") (pinfunction "1_1") (pintype "passive"))
      (node (ref "R66") (pin "1") (pinfunction "1_1") (pintype "passive"))
      (node (ref "R67") (pin "1") (pinfunction "1_1") (pintype "passive"))
      (node (ref "SJ1") (pin "P$2") (pinfunction "2_P$2") (pintype "passive"))
      (node (ref "SJ10") (pin "P$2") (pinfunction "2_P$2") (pintype "passive"))
      (node (ref "SJ4") (pin "P$2") (pinfunction "2_P$2") (pintype "passive"))
      (node (ref "SJ7") (pin "P$2") (pinfunction "2_P$2") (pintype "passive"))
      (node (ref "U$1") (pin "5V2") (pinfunction "5V2_5V2") (pintype "power_in"))
      (node (ref "U7") (pin "3") (pinfunction "VCC_3") (pintype "power_in"))
      (node (ref "U7B") (pin "3") (pinfunction "VDD_3") (pintype "power_in"))
      (node (ref "X1") (pin "1") (pinfunction "1_1") (pintype "passive"))
    )
    (net (code "3") (name "+12V") (class "Default")
      (node (ref "C10") (pin "1") (pinfunction "1_1") (pintype "passive"))
      (node (ref "C6") (pin "1") (pinfunction "1_1") (pintype "passive"))
      (node (ref "C7") (pin "1") (pinfunction "1_1") (pintype "passive"))
      (node (ref "IC6") (pin "4") (pinfunction "V+_4") (pintype "power_in"))
      (node (ref "IC9") (pin "4") (pinfunction "V+_4") (pintype "power_in"))
      (node (ref "J3") (pin "1") (pinfunction "1_1") (pintype "passive"))
      (node (ref "JP10") (pin "3") (pinfunction "3_3") (pintype "passive"))
      (node (ref "JP4") (pin "2") (pinfunction "2_2") (pintype "passive"))
      (node (ref "SJ11") (pin "P$2") (pinfunction "2_P$2") (pintype "passive"))
      (node (ref "SJ14") (pin "P$2") (pinfunction "2_P$2") (pintype "passive"))
      (node (ref "SJ2") (pin "P$2") (pinfunction "2_P$2") (pintype "passive"))
      (node (ref "SJ5") (pin "P$2") (pinfunction "2_P$2") (pintype "passive"))
      (node (ref "SJ8") (pin "P$2") (pinfunction "2_P$2") (pintype "passive"))
      (node (ref "U$2") (pin "6") (pinfunction "VDD_6") (pintype "power_in"))
      (node (ref "U$3") (pin "6") (pinfunction "VDD_6") (pintype "power_in"))
      (node (ref "U$4") (pin "6") (pinfunction "VDD_6") (pintype "power_in"))
      (node (ref "U$5") (pin "6") (pinfunction "VDD_6") (pintype "power_in"))
      (node (ref "U8") (pin "1") (pinfunction "VIN_1") (pintype "bidirectional"))
      (node (ref "U8B") (pin "5") (pinfunction "IN_5") (pintype "input"))
    )
    (net (code "4") (name "/AGND") (class "Default")
      (node (ref "U$1") (pin "AGND") (pinfunction "AGND_AGND") (pintype "power_in"))
    )
    (net (code "5") (name "/AVDD") (class "Default")
      (node (ref "U$1") (pin "AVDD") (pinfunction "AVDD_AVDD") (pintype "power_in"))
    )
    (net (code "6") (name "/CANH") (class "Default")
      (node (ref "J1") (pin "1") (pinfunction "1_1") (pintype "passive"))
      (node (ref "J2") (pin "1") (pinfunction "1_1") (pintype "passive"))
      (node (ref "U7") (pin "7") (pinfunction "CANH_7") (pintype "bidirectional"))
      (node (ref "U7B") (pin "7") (pinfunction "CANH_7") (pintype "bidirectional"))
    )
    (net (code "7") (name "/CANL") (class "Default")
      (node (ref "J1") (pin "2") (pinfunction "2_2") (pintype "passive"))
      (node (ref "J2") (pin "2") (pinfunction "2_2") (pintype "passive"))
      (node (ref "U7") (pin "6") (pinfunction "CANL_6") (pintype "bidirectional"))
      (node (ref "U7B") (pin "6") (pinfunction "CANL_6") (pintype "bidirectional"))
    )
    (net (code "8") (name "/GND4") (class "Default")
      (node (ref "U$1") (pin "GND4") (pinfunction "GND4_GND4") (pintype "power_in"))
    )
    (net (code "9") (name "/PWR_POS") (class "Default")
      (node (ref "J1") (pin "8") (pinfunction "8_8") (pintype "passive"))
      (node (ref "J2") (pin "8") (pinfunction "8_8") (pintype "passive"))
      (node (ref "R40") (pin "1") (pinfunction "1_1") (pintype "passive"))
    )
    (net (code "10") (name "/U5V") (class "Default")
      (node (ref "U$1") (pin "U5V") (pinfunction "U5V_U5V") (pintype "power_in"))
    )
    (net (code "11") (name "/VBAT") (class "Default")
      (node (ref "U$1") (pin "VBAT") (pinfunction "VBAT_VBAT") (pintype "power_in"))
    )
    (net (code "12") (name "/VDD") (class "Default")
      (node (ref "U$1") (pin "VDD") (pinfunction "VDD_VDD") (pintype "power_in"))
    )
    (net (code "13") (name "CANRX") (class "Default")
      (node (ref "U$1") (pin "PB8") (pinfunction "PB8_PB8") (pintype "bidirectional"))
      (node (ref "U7") (pin "4") (pinfunction "RXD_4") (pintype "output"))
      (node (ref "U7B") (pin "4") (pinfunction "RXD_4") (pintype "bidirectional"))
    )
    (net (code "14") (name "CANTX") (class "Default")
      (node (ref "U$1") (pin "PB9") (pinfunction "PB9_PB9") (pintype "bidirectional"))
      (node (ref "U7") (pin "1") (pinfunction "TXD_1") (pintype "input"))
      (node (ref "U7B") (pin "1") (pinfunction "TXD_1") (pintype "bidirectional"))
    )
    (net (code "15") (name "E_CS") (class "Default")
      (node (ref "JP9") (pin "4") (pinfunction "4_4") (pintype "passive"))
      (node (ref "R23") (pin "2") (pinfunction "2_2") (pintype "passive"))
      (node (ref "U$1") (pin "PC10") (pinfunction "PC10_PC10") (pintype "bidirectional"))
    )
    (net (code "16") (name "E_LAT") (class "Default")
      (node (ref "JP10") (pin "1") (pinfunction "1_1") (pintype "passive"))
      (node (ref "R22") (pin "2") (pinfunction "2_2") (pintype "passive"))
      (node (ref "U$1") (pin "PC11") (pinfunction "PC11_PC11") (pintype "bidirectional"))
    )
    (net (code "17") (name "GND") (class "Default")
      (node (ref "C1") (pin "2") (pinfunction "2_2") (pintype "passive"))
      (node (ref "C10") (pin "2") (pinfunction "2_2") (pintype "passive"))
      (node (ref "C11") (pin "2") (pinfunction "2_2") (pintype "passive"))
      (node (ref "C2") (pin "-") (pinfunction "-_-") (pintype "passive"))
      (node (ref "C3") (pin "2") (pinfunction "2_2") (pintype "passive"))
      (node (ref "C4") (pin "2") (pinfunction "2_2") (pintype "passive"))
      (node (ref "C5") (pin "2") (pinfunction "2_2") (pintype "passive"))
      (node (ref "C6") (pin "2") (pinfunction "2_2") (pintype "passive"))
      (node (ref "C7") (pin "2") (pinfunction "2_2") (pintype "passive"))
      (node (ref "C8") (pin "2") (pinfunction "2_2") (pintype "passive"))
      (node (ref "C9") (pin "2") (pinfunction "2_2") (pintype "passive"))
      (node (ref "D1") (pin "A") (pinfunction "A_A") (pintype "passive"))
      (node (ref "IC1") (pin "6") (pinfunction "INH_6") (pintype "input"))
      (node (ref "IC1") (pin "8") (pinfunction "GND_8") (pintype "power_in"))
      (node (ref "IC3") (pin "13") (pinfunction "G_13") (pintype "input"))
      (node (ref "IC3") (pin "8") (pinfunction "GND_8") (pintype "power_in"))
      (node (ref "IC4") (pin "6") (pinfunction "INH_6") (pintype "input"))
      (node (ref "IC4") (pin "8") (pinfunction "GND_8") (pintype "power_in"))
      (node (ref "IC5") (pin "13") (pinfunction "G_13") (pintype "input"))
      (node (ref "IC5") (pin "8") (pinfunction "GND_8") (pintype "power_in"))
      (node (ref "IC6") (pin "11") (pinfunction "V-_11") (pintype "power_in"))
      (node (ref "IC9") (pin "11") (pinfunction "V-_11") (pintype "power_in"))
      (node (ref "J1") (pin "3") (pinfunction "3_3") (pintype "passive"))
      (node (ref "J1") (pin "6") (pinfunction "6_6") (pintype "passive"))
      (node (ref "J1") (pin "7") (pinfunction "7_7") (pintype "passive"))
      (node (ref "J2") (pin "3") (pinfunction "3_3") (pintype "passive"))
      (node (ref "J2") (pin "6") (pinfunction "6_6") (pintype "passive"))
      (node (ref "J2") (pin "7") (pinfunction "7_7") (pintype "passive"))
      (node (ref "J3") (pin "2") (pinfunction "2_2") (pintype "passive"))
      (node (ref "J3") (pin "3") (pinfunction "3_3") (pintype "passive"))
      (node (ref "JP10") (pin "4") (pinfunction "4_4") (pintype "passive"))
      (node (ref "JP11") (pin "5") (pinfunction "5_5") (pintype "passive"))
      (node (ref "JP11") (pin "6") (pinfunction "6_6") (pintype "passive"))
      (node (ref "JP12") (pin "5") (pinfunction "5_5") (pintype "passive"))
      (node (ref "JP12") (pin "6") (pinfunction "6_6") (pintype "passive"))
      (node (ref "JP13") (pin "5") (pinfunction "5_5") (pintype "passive"))
      (node (ref "JP14") (pin "5") (pinfunction "5_5") (pintype "passive"))
      (node (ref "JP15") (pin "5") (pinfunction "5_5") (pintype "passive"))
      (node (ref "JP16") (pin "5") (pinfunction "5_5") (pintype "passive"))
      (node (ref "JP16") (pin "6") (pinfunction "6_6") (pintype "passive"))
      (node (ref "JP7") (pin "5") (pinfunction "5_5") (pintype "passive"))
      (node (ref "JP7") (pin "6") (pinfunction "6_6") (pintype "passive"))
      (node (ref "JP8") (pin "4") (pinfunction "4_4") (pintype "passive"))
      (node (ref "Q1") (pin "2") (pinfunction "S_2") (pintype "passive"))
      (node (ref "Q10") (pin "2") (pinfunction "S_2") (pintype "passive"))
      (node (ref "Q11") (pin "2") (pinfunction "S_2") (pintype "passive"))
      (node (ref "Q12") (pin "2") (pinfunction "S_2") (pintype "passive"))
      (node (ref "Q13") (pin "2") (pinfunction "S_2") (pintype "passive"))
      (node (ref "Q14") (pin "2") (pinfunction "S_2") (pintype "passive"))
      (node (ref "Q15") (pin "2") (pinfunction "S_2") (pintype "passive"))
      (node (ref "Q16") (pin "2") (pinfunction "S_2") (pintype "passive"))
      (node (ref "Q2") (pin "2") (pinfunction "S_2") (pintype "passive"))
      (node (ref "Q3") (pin "2") (pinfunction "S_2") (pintype "passive"))
      (node (ref "Q4") (pin "2") (pinfunction "S_2") (pintype "passive"))
      (node (ref "Q5") (pin "2") (pinfunction "S_2") (pintype "passive"))
      (node (ref "Q6") (pin "2") (pinfunction "S_2") (pintype "passive"))
      (node (ref "Q7") (pin "2") (pinfunction "S_2") (pintype "passive"))
      (node (ref "Q8") (pin "2") (pinfunction "S_2") (pintype "passive"))
      (node (ref "Q9") (pin "2") (pinfunction "S_2") (pintype "passive"))
      (node (ref "R2") (pin "1") (pinfunction "1_1") (pintype "passive"))
      (node (ref "R61") (pin "2") (pinfunction "2_2") (pintype "passive"))
      (node (ref "SJ12") (pin "P$2") (pinfunction "2_P$2") (pintype "passive"))
      (node (ref "SJ3") (pin "2") (pinfunction "2_2") (pintype "passive"))
      (node (ref "SJ6") (pin "P$2") (pinfunction "2_P$2") (pintype "passive"))
      (node (ref "SJ9") (pin "2") (pinfunction "2_2") (pintype "passive"))
      (node (ref "U$1") (pin "GND3") (pinfunction "GND3_GND3") (pintype "power_in"))
      (node (ref "U$1") (pin "GND5") (pinfunction "GND5_GND5") (pintype "power_in"))
      (node (ref "U$1") (pin "GND6") (pinfunction "GND6_GND6") (pintype "power_in"))
      (node (ref "U$1") (pin "GND7") (pinfunction "GND7_GND7") (pintype "power_in"))
      (node (ref "U$1") (pin "GND8") (pinfunction "GND8_GND8") (pintype "power_in"))
      (node (ref "U$2") (pin "3") (pinfunction "VSS_3") (pintype "power_in"))
      (node (ref "U$3") (pin "3") (pinfunction "VSS_3") (pintype "power_in"))
      (node (ref "U$4") (pin "3") (pinfunction "VSS_3") (pintype "power_in"))
      (node (ref "U$5") (pin "3") (pinfunction "VSS_3") (pintype "power_in"))
      (node (ref "U7") (pin "2") (pinfunction "GND_2") (pintype "power_in"))
      (node (ref "U7B") (pin "2") (pinfunction "VSS_2") (pintype "power_in"))
      (node (ref "U8") (pin "4") (pinfunction "SD_4") (pintype "bidirectional"))
      (node (ref "U8") (pin "5") (pinfunction "GND1_5") (pintype "power_in"))
      (node (ref "U8") (pin "6") (pinfunction "GND2_6") (pintype "power_in"))
      (node (ref "U8") (pin "7") (pinfunction "GND3_7") (pintype "power_in"))
      (node (ref "U8") (pin "8") (pinfunction "GND4_8") (pintype "power_in"))
      (node (ref "U8B") (pin "2") (pinfunction "GNDSIG_2") (pintype "input"))
      (node (ref "U8B") (pin "3") (pinfunction "~{ON/OFF}_3") (pintype "input"))
      (node (ref "U8B") (pin "4") (pinfunction "GND_4") (pintype "power_in"))
      (node (ref "X1") (pin "2") (pinfunction "2_2") (pintype "passive"))
    )
    (net (code "18") (name "I2CSCL") (class "Default")
      (node (ref "JP8") (pin "2") (pinfunction "2_2") (pintype "passive"))
      (node (ref "R63") (pin "2") (pinfunction "2_2") (pintype "passive"))
      (node (ref "U$1") (pin "PB6") (pinfunction "PB6_PB6") (pintype "bidirectional"))
    )
    (net (code "19") (name "I2CSDA") (class "Default")
      (node (ref "JP8") (pin "1") (pinfunction "1_1") (pintype "passive"))
      (node (ref "R62") (pin "2") (pinfunction "2_2") (pintype "passive"))
      (node (ref "U$1") (pin "PB7") (pinfunction "PB7_PB7") (pintype "bidirectional"))
    )
    (net (code "20") (name "ILAT") (class "Default")
      (node (ref "IC1") (pin "15") (pinfunction "SH/~{LD}_15") (pintype "input"))
      (node (ref "IC4") (pin "15") (pinfunction "SH/~{LD}_15") (pintype "input"))
      (node (ref "U$1") (pin "PA6") (pinfunction "PA6_PA6") (pintype "bidirectional"))
    )
    (net (code "21") (name "MISO") (class "Default")
      (node (ref "JP9") (pin "1") (pinfunction "1_1") (pintype "passive"))
      (node (ref "U$1") (pin "PB4") (pinfunction "PB4_PB4") (pintype "bidirectional"))
    )
    (net (code "22") (name "MISO2") (class "Default")
      (node (ref "IC4") (pin "13") (pinfunction "QH_13") (pintype "output"))
      (node (ref "SJ13") (pin "P$2") (pinfunction "2_P$2") (pintype "passive"))
      (node (ref "U$1") (pin "PC2") (pinfunction "PC2_PC2") (pintype "bidirectional"))
    )
    (net (code "23") (name "MOSI") (class "Default")
      (node (ref "IC5") (pin "14") (pinfunction "SER_14") (pintype "input"))
      (node (ref "R20") (pin "1") (pinfunction "1_1") (pintype "passive"))
      (node (ref "SJ15") (pin "1") (pinfunction "1_1") (pintype "passive"))
      (node (ref "SJ17") (pin "P$2") (pinfunction "2_P$2") (pintype "passive"))
      (node (ref "U$1") (pin "PB5") (pinfunction "PB5_PB5") (pintype "bidirectional"))
    )
    (net (code "24") (name "Net-(D2-PadA)") (class "Default")
      (node (ref "D2") (pin "A") (pinfunction "A_A") (pintype "passive"))
      (node (ref "JP4") (pin "4") (pinfunction "4_4") (pintype "passive"))
    )
    (net (code "25") (name "Net-(D2-PadC)") (class "Default")
      (node (ref "D2") (pin "C") (pinfunction "C_C") (pintype "passive"))
      (node (ref "JP4") (pin "1") (pinfunction "1_1") (pintype "passive"))
    )
    (net (code "26") (name "Net-(IC1A-A)") (class "Default")
      (node (ref "IC1") (pin "2") (pinfunction "A_2") (pintype "input"))
      (node (ref "R36") (pin "1") (pinfunction "1_1") (pintype "passive"))
      (node (ref "RN4") (pin "9") (pinfunction "2_9") (pintype "passive"))
    )
    (net (code "27") (name "Net-(IC1A-B)") (class "Default")
      (node (ref "IC1") (pin "3") (pinfunction "B_3") (pintype "input"))
      (node (ref "R37") (pin "1") (pinfunction "1_1") (pintype "passive"))
      (node (ref "RN4") (pin "10") (pinfunction "2_10") (pintype "passive"))
    )
    (net (code "28") (name "Net-(IC1A-C)") (class "Default")
      (node (ref "IC1") (pin "4") (pinfunction "C_4") (pintype "input"))
      (node (ref "R38") (pin "1") (pinfunction "1_1") (pintype "passive"))
      (node (ref "RN4") (pin "11") (pinfunction "2_11") (pintype "passive"))
    )
    (net (code "29") (name "Net-(IC1A-D)") (class "Default")
      (node (ref "IC1") (pin "5") (pinfunction "D_5") (pintype "input"))
      (node (ref "R39") (pin "1") (pinfunction "1_1") (pintype "passive"))
      (node (ref "RN4") (pin "12") (pinfunction "2_12") (pintype "passive"))
    )
    (net (code "30") (name "Net-(IC1A-E)") (class "Default")
      (node (ref "IC1") (pin "10") (pinfunction "E_10") (pintype "input"))
      (node (ref "R41") (pin "1") (pinfunction "1_1") (pintype "passive"))
      (node (ref "RN4") (pin "13") (pinfunction "2_13") (pintype "passive"))
    )
    (net (code "31") (name "Net-(IC1A-F)") (class "Default")
      (node (ref "IC1") (pin "11") (pinfunction "F_11") (pintype "input"))
      (node (ref "R42") (pin "1") (pinfunction "1_1") (pintype "passive"))
      (node (ref "RN4") (pin "14") (pinfunction "2_14") (pintype "passive"))
    )
    (net (code "32") (name "Net-(IC1A-G)") (class "Default")
      (node (ref "IC1") (pin "12") (pinfunction "G_12") (pintype "input"))
      (node (ref "R43") (pin "1") (pinfunction "1_1") (pintype "passive"))
      (node (ref "RN4") (pin "15") (pinfunction "2_15") (pintype "passive"))
    )
    (net (code "33") (name "Net-(IC1A-H)") (class "Default")
      (node (ref "IC1") (pin "14") (pinfunction "H_14") (pintype "input"))
      (node (ref "R44") (pin "1") (pinfunction "1_1") (pintype "passive"))
      (node (ref "RN4") (pin "16") (pinfunction "2_16") (pintype "passive"))
    )
    (net (code "34") (name "Net-(IC2-CD+)") (class "Default")
      (node (ref "IC2") (pin "10") (pinfunction "CD+_10") (pintype "passive"))
      (node (ref "SJ4") (pin "P$1") (pinfunction "1_P$1") (pintype "passive"))
      (node (ref "SJ5") (pin "P$1") (pinfunction "1_P$1") (pintype "passive"))
      (node (ref "SJ6") (pin "P$1") (pinfunction "1_P$1") (pintype "passive"))
    )
    (net (code "35") (name "Net-(IC2-GND)") (class "Default")
      (node (ref "IC2") (pin "9") (pinfunction "GND_9") (pintype "power_in"))
      (node (ref "SJ1") (pin "P$1") (pinfunction "1_P$1") (pintype "passive"))
      (node (ref "SJ2") (pin "P$1") (pinfunction "1_P$1") (pintype "passive"))
      (node (ref "SJ3") (pin "1") (pinfunction "1_1") (pintype "passive"))
    )
    (net (code "36") (name "Net-(IC2-I1)") (class "Default")
      (node (ref "IC2") (pin "1") (pinfunction "I1_1") (pintype "input"))
      (node (ref "IC5") (pin "15") (pinfunction "QA_15") (pintype "tri_state"))
      (node (ref "R3") (pin "1") (pinfunction "1_1") (pintype "passive"))
    )
    (net (code "37") (name "Net-(IC2-I2)") (class "Default")
      (node (ref "IC2") (pin "2") (pinfunction "I2_2") (pintype "input"))
      (node (ref "IC5") (pin "1") (pinfunction "QB_1") (pintype "tri_state"))
      (node (ref "R4") (pin "1") (pinfunction "1_1") (pintype "passive"))
    )
    (net (code "38") (name "Net-(IC2-I3)") (class "Default")
      (node (ref "IC2") (pin "3") (pinfunction "I3_3") (pintype "input"))
      (node (ref "IC5") (pin "2") (pinfunction "QC_2") (pintype "tri_state"))
      (node (ref "R5") (pin "1") (pinfunction "1_1") (pintype "passive"))
    )
    (net (code "39") (name "Net-(IC2-I4)") (class "Default")
      (node (ref "IC2") (pin "4") (pinfunction "I4_4") (pintype "input"))
      (node (ref "IC5") (pin "3") (pinfunction "QD_3") (pintype "tri_state"))
      (node (ref "R6") (pin "1") (pinfunction "1_1") (pintype "passive"))
    )
    (net (code "40") (name "Net-(IC2-I5)") (class "Default")
      (node (ref "IC2") (pin "5") (pinfunction "I5_5") (pintype "input"))
      (node (ref "IC5") (pin "4") (pinfunction "QE_4") (pintype "tri_state"))
      (node (ref "R7") (pin "1") (pinfunction "1_1") (pintype "passive"))
    )
    (net (code "41") (name "Net-(IC2-I6)") (class "Default")
      (node (ref "IC2") (pin "6") (pinfunction "I6_6") (pintype "input"))
      (node (ref "IC5") (pin "5") (pinfunction "QF_5") (pintype "tri_state"))
      (node (ref "R8") (pin "1") (pinfunction "1_1") (pintype "passive"))
    )
    (net (code "42") (name "Net-(IC2-I7)") (class "Default")
      (node (ref "IC2") (pin "7") (pinfunction "I7_7") (pintype "input"))
      (node (ref "IC5") (pin "6") (pinfunction "QG_6") (pintype "tri_state"))
      (node (ref "R9") (pin "1") (pinfunction "1_1") (pintype "passive"))
    )
    (net (code "43") (name "Net-(IC2-I8)") (class "Default")
      (node (ref "IC2") (pin "8") (pinfunction "I8_8") (pintype "input"))
      (node (ref "IC5") (pin "7") (pinfunction "QH_7") (pintype "tri_state"))
      (node (ref "R10") (pin "1") (pinfunction "1_1") (pintype "passive"))
    )
    (net (code "44") (name "Net-(IC2-O1)") (class "Default")
      (node (ref "IC2") (pin "18") (pinfunction "O1_18") (pintype "open_collector"))
      (node (ref "JP1") (pin "1") (pinfunction "1_1") (pintype "passive"))
      (node (ref "Q1") (pin "3") (pinfunction "D_3") (pintype "passive"))
    )
    (net (code "45") (name "Net-(IC2-O2)") (class "Default")
      (node (ref "IC2") (pin "17") (pinfunction "O2_17") (pintype "open_collector"))
      (node (ref "JP1") (pin "2") (pinfunction "2_2") (pintype "passive"))
      (node (ref "Q2") (pin "3") (pinfunction "D_3") (pintype "passive"))
    )
    (net (code "46") (name "Net-(IC2-O3)") (class "Default")
      (node (ref "IC2") (pin "16") (pinfunction "O3_16") (pintype "open_collector"))
      (node (ref "JP1") (pin "3") (pinfunction "3_3") (pintype "passive"))
      (node (ref "Q3") (pin "3") (pinfunction "D_3") (pintype "passive"))
    )
    (net (code "47") (name "Net-(IC2-O4)") (class "Default")
      (node (ref "IC2") (pin "15") (pinfunction "O4_15") (pintype "open_collector"))
      (node (ref "JP1") (pin "4") (pinfunction "4_4") (pintype "passive"))
      (node (ref "Q4") (pin "3") (pinfunction "D_3") (pintype "passive"))
    )
    (net (code "48") (name "Net-(IC2-O5)") (class "Default")
      (node (ref "IC2") (pin "14") (pinfunction "O5_14") (pintype "open_collector"))
      (node (ref "JP1") (pin "5") (pinfunction "5_5") (pintype "passive"))
      (node (ref "Q5") (pin "3") (pinfunction "D_3") (pintype "passive"))
    )
    (net (code "49") (name "Net-(IC2-O6)") (class "Default")
      (node (ref "IC2") (pin "13") (pinfunction "O6_13") (pintype "open_collector"))
      (node (ref "JP1") (pin "6") (pinfunction "6_6") (pintype "passive"))
      (node (ref "Q6") (pin "3") (pinfunction "D_3") (pintype "passive"))
    )
    (net (code "50") (name "Net-(IC2-O7)") (class "Default")
      (node (ref "IC2") (pin "12") (pinfunction "O7_12") (pintype "open_collector"))
      (node (ref "JP1") (pin "7") (pinfunction "7_7") (pintype "passive"))
      (node (ref "Q7") (pin "3") (pinfunction "D_3") (pintype "passive"))
    )
    (net (code "51") (name "Net-(IC2-O8)") (class "Default")
      (node (ref "IC2") (pin "11") (pinfunction "O8_11") (pintype "open_collector"))
      (node (ref "JP1") (pin "8") (pinfunction "8_8") (pintype "passive"))
      (node (ref "Q8") (pin "3") (pinfunction "D_3") (pintype "passive"))
    )
    (net (code "52") (name "Net-(IC3A-QA)") (class "Default")
      (node (ref "IC3") (pin "15") (pinfunction "QA_15") (pintype "tri_state"))
      (node (ref "IC8") (pin "1") (pinfunction "I1_1") (pintype "input"))
      (node (ref "R11") (pin "1") (pinfunction "1_1") (pintype "passive"))
    )
    (net (code "53") (name "Net-(IC3A-QB)") (class "Default")
      (node (ref "IC3") (pin "1") (pinfunction "QB_1") (pintype "tri_state"))
      (node (ref "IC8") (pin "2") (pinfunction "I2_2") (pintype "input"))
      (node (ref "R12") (pin "1") (pinfunction "1_1") (pintype "passive"))
    )
    (net (code "54") (name "Net-(IC3A-QC)") (class "Default")
      (node (ref "IC3") (pin "2") (pinfunction "QC_2") (pintype "tri_state"))
      (node (ref "IC8") (pin "3") (pinfunction "I3_3") (pintype "input"))
      (node (ref "R13") (pin "1") (pinfunction "1_1") (pintype "passive"))
    )
    (net (code "55") (name "Net-(IC3A-QD)") (class "Default")
      (node (ref "IC3") (pin "3") (pinfunction "QD_3") (pintype "tri_state"))
      (node (ref "IC8") (pin "4") (pinfunction "I4_4") (pintype "input"))
      (node (ref "R14") (pin "1") (pinfunction "1_1") (pintype "passive"))
    )
    (net (code "56") (name "Net-(IC3A-QE)") (class "Default")
      (node (ref "IC3") (pin "4") (pinfunction "QE_4") (pintype "tri_state"))
      (node (ref "IC8") (pin "5") (pinfunction "I5_5") (pintype "input"))
      (node (ref "R15") (pin "1") (pinfunction "1_1") (pintype "passive"))
    )
    (net (code "57") (name "Net-(IC3A-QF)") (class "Default")
      (node (ref "IC3") (pin "5") (pinfunction "QF_5") (pintype "tri_state"))
      (node (ref "IC8") (pin "6") (pinfunction "I6_6") (pintype "input"))
      (node (ref "R16") (pin "1") (pinfunction "1_1") (pintype "passive"))
    )
    (net (code "58") (name "Net-(IC3A-QG)") (class "Default")
      (node (ref "IC3") (pin "6") (pinfunction "QG_6") (pintype "tri_state"))
      (node (ref "IC8") (pin "7") (pinfunction "I7_7") (pintype "input"))
      (node (ref "R17") (pin "1") (pinfunction "1_1") (pintype "passive"))
    )
    (net (code "59") (name "Net-(IC3A-QH)") (class "Default")
      (node (ref "IC3") (pin "7") (pinfunction "QH_7") (pintype "tri_state"))
      (node (ref "IC8") (pin "8") (pinfunction "I8_8") (pintype "input"))
      (node (ref "R18") (pin "1") (pinfunction "1_1") (pintype "passive"))
    )
    (net (code "60") (name "Net-(IC4A-A)") (class "Default")
      (node (ref "IC4") (pin "2") (pinfunction "A_2") (pintype "input"))
      (node (ref "R28") (pin "1") (pinfunction "1_1") (pintype "passive"))
      (node (ref "RN1") (pin "9") (pinfunction "2_9") (pintype "passive"))
    )
    (net (code "61") (name "Net-(IC4A-B)") (class "Default")
      (node (ref "IC4") (pin "3") (pinfunction "B_3") (pintype "input"))
      (node (ref "R29") (pin "1") (pinfunction "1_1") (pintype "passive"))
      (node (ref "RN1") (pin "10") (pinfunction "2_10") (pintype "passive"))
    )
    (net (code "62") (name "Net-(IC4A-C)") (class "Default")
      (node (ref "IC4") (pin "4") (pinfunction "C_4") (pintype "input"))
      (node (ref "R30") (pin "1") (pinfunction "1_1") (pintype "passive"))
      (node (ref "RN1") (pin "11") (pinfunction "2_11") (pintype "passive"))
    )
    (net (code "63") (name "Net-(IC4A-D)") (class "Default")
      (node (ref "IC4") (pin "5") (pinfunction "D_5") (pintype "input"))
      (node (ref "R31") (pin "1") (pinfunction "1_1") (pintype "passive"))
      (node (ref "RN1") (pin "12") (pinfunction "2_12") (pintype "passive"))
    )
    (net (code "64") (name "Net-(IC4A-E)") (class "Default")
      (node (ref "IC4") (pin "10") (pinfunction "E_10") (pintype "input"))
      (node (ref "R32") (pin "1") (pinfunction "1_1") (pintype "passive"))
      (node (ref "RN1") (pin "13") (pinfunction "2_13") (pintype "passive"))
    )
    (net (code "65") (name "Net-(IC4A-F)") (class "Default")
      (node (ref "IC4") (pin "11") (pinfunction "F_11") (pintype "input"))
      (node (ref "R33") (pin "1") (pinfunction "1_1") (pintype "passive"))
      (node (ref "RN1") (pin "14") (pinfunction "2_14") (pintype "passive"))
    )
    (net (code "66") (name "Net-(IC4A-G)") (class "Default")
      (node (ref "IC4") (pin "12") (pinfunction "G_12") (pintype "input"))
      (node (ref "R34") (pin "1") (pinfunction "1_1") (pintype "passive"))
      (node (ref "RN1") (pin "15") (pinfunction "2_15") (pintype "passive"))
    )
    (net (code "67") (name "Net-(IC4A-H)") (class "Default")
      (node (ref "IC4") (pin "14") (pinfunction "H_14") (pintype "input"))
      (node (ref "R35") (pin "1") (pinfunction "1_1") (pintype "passive"))
      (node (ref "RN1") (pin "16") (pinfunction "2_16") (pintype "passive"))
    )
    (net (code "68") (name "Net-(IC6A--IN)") (class "Default")
      (node (ref "IC6") (pin "13") (pinfunction "-IN_13") (pintype "input"))
      (node (ref "IC6") (pin "2") (pinfunction "-IN_2") (pintype "input"))
      (node (ref "IC6") (pin "6") (pinfunction "-IN_6") (pintype "input"))
      (node (ref "IC6") (pin "9") (pinfunction "-IN_9") (pintype "input"))
      (node (ref "IC9") (pin "13") (pinfunction "-IN_13") (pintype "input"))
      (node (ref "IC9") (pin "2") (pinfunction "-IN_2") (pintype "input"))
      (node (ref "IC9") (pin "6") (pinfunction "-IN_6") (pintype "input"))
      (node (ref "IC9") (pin "9") (pinfunction "-IN_9") (pintype "input"))
      (node (ref "R1") (pin "1") (pinfunction "1_1") (pintype "passive"))
      (node (ref "R2") (pin "2") (pinfunction "2_2") (pintype "passive"))
    )
    (net (code "69") (name "Net-(IC6A-OUT)") (class "Default")
      (node (ref "IC6") (pin "1") (pinfunction "OUT_1") (pintype "output"))
      (node (ref "JP15") (pin "3") (pinfunction "3_3") (pintype "passive"))
      (node (ref "JP5") (pin "3") (pinfunction "3_3") (pintype "passive"))
      (node (ref "U$5") (pin "5") (pinfunction "O_5") (pintype "output"))
    )
    (net (code "70") (name "Net-(IC6B-OUT)") (class "Default")
      (node (ref "IC6") (pin "7") (pinfunction "OUT_7") (pintype "output"))
      (node (ref "JP15") (pin "1") (pinfunction "1_1") (pintype "passive"))
      (node (ref "JP5") (pin "1") (pinfunction "1_1") (pintype "passive"))
      (node (ref "U$4") (pin "7") (pinfunction "O_7") (pintype "output"))
    )
    (net (code "71") (name "Net-(IC6C-OUT)") (class "Default")
      (node (ref "IC6") (pin "8") (pinfunction "OUT_8") (pintype "output"))
      (node (ref "JP15") (pin "2") (pinfunction "2_2") (pintype "passive"))
      (node (ref "JP5") (pin "2") (pinfunction "2_2") (pintype "passive"))
      (node (ref "U$4") (pin "5") (pinfunction "O_5") (pintype "output"))
    )
    (net (code "72") (name "Net-(IC6D-OUT)") (class "Default")
      (node (ref "IC6") (pin "14") (pinfunction "OUT_14") (pintype "output"))
      (node (ref "JP15") (pin "4") (pinfunction "4_4") (pintype "passive"))
      (node (ref "JP5") (pin "4") (pinfunction "4_4") (pintype "passive"))
      (node (ref "U$5") (pin "7") (pinfunction "O_7") (pintype "output"))
    )
    (net (code "73") (name "Net-(IC8-CD+)") (class "Default")
      (node (ref "IC8") (pin "10") (pinfunction "CD+_10") (pintype "passive"))
      (node (ref "SJ10") (pin "P$1") (pinfunction "1_P$1") (pintype "passive"))
      (node (ref "SJ11") (pin "P$1") (pinfunction "1_P$1") (pintype "passive"))
      (node (ref "SJ12") (pin "P$1") (pinfunction "1_P$1") (pintype "passive"))
    )
    (net (code "74") (name "Net-(IC8-GND)") (class "Default")
      (node (ref "IC8") (pin "9") (pinfunction "GND_9") (pintype "power_in"))
      (node (ref "SJ7") (pin "P$1") (pinfunction "1_P$1") (pintype "passive"))
      (node (ref "SJ8") (pin "P$1") (pinfunction "1_P$1") (pintype "passive"))
      (node (ref "SJ9") (pin "1") (pinfunction "1_1") (pintype "passive"))
    )
    (net (code "75") (name "Net-(IC8-O1)") (class "Default")
      (node (ref "IC8") (pin "18") (pinfunction "O1_18") (pintype "open_collector"))
      (node (ref "JP6") (pin "1") (pinfunction "1_1") (pintype "passive"))
      (node (ref "Q9") (pin "3") (pinfunction "D_3") (pintype "passive"))
    )
    (net (code "76") (name "Net-(IC8-O2)") (class "Default")
      (node (ref "IC8") (pin "17") (pinfunction "O2_17") (pintype "open_collector"))
      (node (ref "JP6") (pin "2") (pinfunction "2_2") (pintype "passive"))
      (node (ref "Q10") (pin "3") (pinfunction "D_3") (pintype "passive"))
    )
    (net (code "77") (name "Net-(IC8-O3)") (class "Default")
      (node (ref "IC8") (pin "16") (pinfunction "O3_16") (pintype "open_collector"))
      (node (ref "JP6") (pin "3") (pinfunction "3_3") (pintype "passive"))
      (node (ref "Q11") (pin "3") (pinfunction "D_3") (pintype "passive"))
    )
    (net (code "78") (name "Net-(IC8-O4)") (class "Default")
      (node (ref "IC8") (pin "15") (pinfunction "O4_15") (pintype "open_collector"))
      (node (ref "JP6") (pin "4") (pinfunction "4_4") (pintype "passive"))
      (node (ref "Q12") (pin "3") (pinfunction "D_3") (pintype "passive"))
    )
    (net (code "79") (name "Net-(IC8-O5)") (class "Default")
      (node (ref "IC8") (pin "14") (pinfunction "O5_14") (pintype "open_collector"))
      (node (ref "JP6") (pin "5") (pinfunction "5_5") (pintype "passive"))
      (node (ref "Q13") (pin "3") (pinfunction "D_3") (pintype "passive"))
    )
    (net (code "80") (name "Net-(IC8-O6)") (class "Default")
      (node (ref "IC8") (pin "13") (pinfunction "O6_13") (pintype "open_collector"))
      (node (ref "JP6") (pin "6") (pinfunction "6_6") (pintype "passive"))
      (node (ref "Q14") (pin "3") (pinfunction "D_3") (pintype "passive"))
    )
    (net (code "81") (name "Net-(IC8-O7)") (class "Default")
      (node (ref "IC8") (pin "12") (pinfunction "O7_12") (pintype "open_collector"))
      (node (ref "JP6") (pin "7") (pinfunction "7_7") (pintype "passive"))
      (node (ref "Q15") (pin "3") (pinfunction "D_3") (pintype "passive"))
    )
    (net (code "82") (name "Net-(IC8-O8)") (class "Default")
      (node (ref "IC8") (pin "11") (pinfunction "O8_11") (pintype "open_collector"))
      (node (ref "JP6") (pin "8") (pinfunction "8_8") (pintype "passive"))
      (node (ref "Q16") (pin "3") (pinfunction "D_3") (pintype "passive"))
    )
    (net (code "83") (name "Net-(IC9A-OUT)") (class "Default")
      (node (ref "IC9") (pin "1") (pinfunction "OUT_1") (pintype "output"))
      (node (ref "JP15") (pin "9") (pinfunction "9_9") (pintype "passive"))
      (node (ref "JP5") (pin "7") (pinfunction "7_7") (pintype "passive"))
      (node (ref "U$3") (pin "5") (pinfunction "O_5") (pintype "output"))
    )
    (net (code "84") (name "Net-(IC9B-OUT)") (class "Default")
      (node (ref "IC9") (pin "7") (pinfunction "OUT_7") (pintype "output"))
      (node (ref "JP15") (pin "7") (pinfunction "7_7") (pintype "passive"))
      (node (ref "JP5") (pin "5") (pinfunction "5_5") (pintype "passive"))
      (node (ref "U$2") (pin "7") (pinfunction "O_7") (pintype "output"))
    )
    (net (code "85") (name "Net-(IC9C-OUT)") (class "Default")
      (node (ref "IC9") (pin "8") (pinfunction "OUT_8") (pintype "output"))
      (node (ref "JP15") (pin "8") (pinfunction "8_8") (pintype "passive"))
      (node (ref "JP5") (pin "6") (pinfunction "6_6") (pintype "passive"))
      (node (ref "U$2") (pin "5") (pinfunction "O_5") (pintype "output"))
    )
    (net (code "86") (name "Net-(IC9D-OUT)") (class "Default")
      (node (ref "IC9") (pin "14") (pinfunction "OUT_14") (pintype "output"))
      (node (ref "JP15") (pin "10") (pinfunction "10_10") (pintype "passive"))
      (node (ref "JP5") (pin "8") (pinfunction "8_8") (pintype "passive"))
      (node (ref "U$3") (pin "7") (pinfunction "O_7") (pintype "output"))
    )
    (net (code "87") (name "Net-(J1-Pad4)") (class "Default")
      (node (ref "J1") (pin "4") (pinfunction "4_4") (pintype "passive"))
      (node (ref "J2") (pin "4") (pinfunction "4_4") (pintype "passive"))
    )
    (net (code "88") (name "Net-(J1-Pad5)") (class "Default")
      (node (ref "J1") (pin "5") (pinfunction "5_5") (pintype "passive"))
      (node (ref "J2") (pin "5") (pinfunction "5_5") (pintype "passive"))
    )
    (net (code "89") (name "Net-(JP4-Pad3)") (class "Default")
      (node (ref "JP4") (pin "3") (pinfunction "3_3") (pintype "passive"))
      (node (ref "R40") (pin "2") (pinfunction "2_2") (pintype "passive"))
    )
    (net (code "90") (name "Net-(JP13-Pad1)") (class "Default")
      (node (ref "JP13") (pin "1") (pinfunction "1_1") (pintype "passive"))
      (node (ref "JP3") (pin "1") (pinfunction "1_1") (pintype "passive"))
      (node (ref "R44") (pin "2") (pinfunction "2_2") (pintype "passive"))
      (node (ref "R53") (pin "2") (pinfunction "2_2") (pintype "passive"))
      (node (ref "RN4") (pin "1") (pinfunction "1_1") (pintype "passive"))
      (node (ref "RN5") (pin "9") (pinfunction "9_9") (pintype "passive"))
    )
    (net (code "91") (name "Net-(JP14-Pad1)") (class "Default")
      (node (ref "JP14") (pin "1") (pinfunction "1_1") (pintype "passive"))
      (node (ref "JP2") (pin "1") (pinfunction "1_1") (pintype "passive"))
      (node (ref "R35") (pin "2") (pinfunction "2_2") (pintype "passive"))
      (node (ref "R45") (pin "2") (pinfunction "2_2") (pintype "passive"))
      (node (ref "RN1") (pin "1") (pinfunction "1_1") (pintype "passive"))
      (node (ref "RN2") (pin "9") (pinfunction "9_9") (pintype "passive"))
    )
    (net (code "92") (name "Net-(Q1-G)") (class "Default")
      (node (ref "Q1") (pin "1") (pinfunction "G_1") (pintype "passive"))
      (node (ref "R3") (pin "2") (pinfunction "2_2") (pintype "passive"))
    )
    (net (code "93") (name "Net-(Q2-G)") (class "Default")
      (node (ref "Q2") (pin "1") (pinfunction "G_1") (pintype "passive"))
      (node (ref "R4") (pin "2") (pinfunction "2_2") (pintype "passive"))
    )
    (net (code "94") (name "Net-(Q3-G)") (class "Default")
      (node (ref "Q3") (pin "1") (pinfunction "G_1") (pintype "passive"))
      (node (ref "R5") (pin "2") (pinfunction "2_2") (pintype "passive"))
    )
    (net (code "95") (name "Net-(Q4-G)") (class "Default")
      (node (ref "Q4") (pin "1") (pinfunction "G_1") (pintype "passive"))
      (node (ref "R6") (pin "2") (pinfunction "2_2") (pintype "passive"))
    )
    (net (code "96") (name "Net-(Q5-G)") (class "Default")
      (node (ref "Q5") (pin "1") (pinfunction "G_1") (pintype "passive"))
      (node (ref "R7") (pin "2") (pinfunction "2_2") (pintype "passive"))
    )
    (net (code "97") (name "Net-(Q6-G)") (class "Default")
      (node (ref "Q6") (pin "1") (pinfunction "G_1") (pintype "passive"))
      (node (ref "R8") (pin "2") (pinfunction "2_2") (pintype "passive"))
    )
    (net (code "98") (name "Net-(Q7-G)") (class "Default")
      (node (ref "Q7") (pin "1") (pinfunction "G_1") (pintype "passive"))
      (node (ref "R9") (pin "2") (pinfunction "2_2") (pintype "passive"))
    )
    (net (code "99") (name "Net-(Q8-G)") (class "Default")
      (node (ref "Q8") (pin "1") (pinfunction "G_1") (pintype "passive"))
      (node (ref "R10") (pin "2") (pinfunction "2_2") (pintype "passive"))
    )
    (net (code "100") (name "Net-(Q9-G)") (class "Default")
      (node (ref "Q9") (pin "1") (pinfunction "G_1") (pintype "passive"))
      (node (ref "R11") (pin "2") (pinfunction "2_2") (pintype "passive"))
    )
    (net (code "101") (name "Net-(Q10-G)") (class "Default")
      (node (ref "Q10") (pin "1") (pinfunction "G_1") (pintype "passive"))
      (node (ref "R12") (pin "2") (pinfunction "2_2") (pintype "passive"))
    )
    (net (code "102") (name "Net-(Q11-G)") (class "Default")
      (node (ref "Q11") (pin "1") (pinfunction "G_1") (pintype "passive"))
      (node (ref "R13") (pin "2") (pinfunction "2_2") (pintype "passive"))
    )
    (net (code "103") (name "Net-(Q12-G)") (class "Default")
      (node (ref "Q12") (pin "1") (pinfunction "G_1") (pintype "passive"))
      (node (ref "R14") (pin "2") (pinfunction "2_2") (pintype "passive"))
    )
    (net (code "104") (name "Net-(Q13-G)") (class "Default")
      (node (ref "Q13") (pin "1") (pinfunction "G_1") (pintype "passive"))
      (node (ref "R15") (pin "2") (pinfunction "2_2") (pintype "passive"))
    )
    (net (code "105") (name "Net-(Q14-G)") (class "Default")
      (node (ref "Q14") (pin "1") (pinfunction "G_1") (pintype "passive"))
      (node (ref "R16") (pin "2") (pinfunction "2_2") (pintype "passive"))
    )
    (net (code "106") (name "Net-(Q15-G)") (class "Default")
      (node (ref "Q15") (pin "1") (pinfunction "G_1") (pintype "passive"))
      (node (ref "R17") (pin "2") (pinfunction "2_2") (pintype "passive"))
    )
    (net (code "107") (name "Net-(Q16-G)") (class "Default")
      (node (ref "Q16") (pin "1") (pinfunction "G_1") (pintype "passive"))
      (node (ref "R18") (pin "2") (pinfunction "2_2") (pintype "passive"))
    )
    (net (code "108") (name "Net-(RN1B-1)") (class "Default")
      (node (ref "JP14") (pin "2") (pinfunction "2_2") (pintype "passive"))
      (node (ref "JP2") (pin "2") (pinfunction "2_2") (pintype "passive"))
      (node (ref "R34") (pin "2") (pinfunction "2_2") (pintype "passive"))
      (node (ref "R46") (pin "1") (pinfunction "1_1") (pintype "passive"))
      (node (ref "RN1") (pin "2") (pinfunction "1_2") (pintype "passive"))
      (node (ref "RN2") (pin "8") (pinfunction "8_8") (pintype "passive"))
    )
    (net (code "109") (name "Net-(RN1C-1)") (class "Default")
      (node (ref "JP14") (pin "3") (pinfunction "3_3") (pintype "passive"))
      (node (ref "JP2") (pin "3") (pinfunction "3_3") (pintype "passive"))
      (node (ref "R33") (pin "2") (pinfunction "2_2") (pintype "passive"))
      (node (ref "R47") (pin "1") (pinfunction "1_1") (pintype "passive"))
      (node (ref "RN1") (pin "3") (pinfunction "1_3") (pintype "passive"))
      (node (ref "RN2") (pin "7") (pinfunction "7_7") (pintype "passive"))
    )
    (net (code "110") (name "Net-(RN1D-1)") (class "Default")
      (node (ref "JP14") (pin "4") (pinfunction "4_4") (pintype "passive"))
      (node (ref "JP2") (pin "4") (pinfunction "4_4") (pintype "passive"))
      (node (ref "R32") (pin "2") (pinfunction "2_2") (pintype "passive"))
      (node (ref "R48") (pin "1") (pinfunction "1_1") (pintype "passive"))
      (node (ref "RN1") (pin "4") (pinfunction "1_4") (pintype "passive"))
      (node (ref "RN2") (pin "6") (pinfunction "6_6") (pintype "passive"))
    )
    (net (code "111") (name "Net-(RN1E-1)") (class "Default")
      (node (ref "JP14") (pin "7") (pinfunction "7_7") (pintype "passive"))
      (node (ref "JP2") (pin "5") (pinfunction "5_5") (pintype "passive"))
      (node (ref "R31") (pin "2") (pinfunction "2_2") (pintype "passive"))
      (node (ref "R49") (pin "1") (pinfunction "1_1") (pintype "passive"))
      (node (ref "RN1") (pin "5") (pinfunction "1_5") (pintype "passive"))
      (node (ref "RN2") (pin "5") (pinfunction "5_5") (pintype "passive"))
    )
    (net (code "112") (name "Net-(RN1F-1)") (class "Default")
      (node (ref "JP14") (pin "8") (pinfunction "8_8") (pintype "passive"))
      (node (ref "JP2") (pin "6") (pinfunction "6_6") (pintype "passive"))
      (node (ref "R30") (pin "2") (pinfunction "2_2") (pintype "passive"))
      (node (ref "R50") (pin "1") (pinfunction "1_1") (pintype "passive"))
      (node (ref "RN1") (pin "6") (pinfunction "1_6") (pintype "passive"))
      (node (ref "RN2") (pin "4") (pinfunction "4_4") (pintype "passive"))
    )
    (net (code "113") (name "Net-(RN1G-1)") (class "Default")
      (node (ref "JP14") (pin "9") (pinfunction "9_9") (pintype "passive"))
      (node (ref "JP2") (pin "7") (pinfunction "7_7") (pintype "passive"))
      (node (ref "R29") (pin "2") (pinfunction "2_2") (pintype "passive"))
      (node (ref "R51") (pin "1") (pinfunction "1_1") (pintype "passive"))
      (node (ref "RN1") (pin "7") (pinfunction "1_7") (pintype "passive"))
      (node (ref "RN2") (pin "3") (pinfunction "3_3") (pintype "passive"))
    )
    (net (code "114") (name "Net-(RN1H-1)") (class "Default")
      (node (ref "JP14") (pin "10") (pinfunction "10_10") (pintype "passive"))
      (node (ref "JP2") (pin "8") (pinfunction "8_8") (pintype "passive"))
      (node (ref "R28") (pin "2") (pinfunction "2_2") (pintype "passive"))
      (node (ref "R52") (pin "1") (pinfunction "1_1") (pintype "passive"))
      (node (ref "RN1") (pin "8") (pinfunction "1_8") (pintype "passive"))
      (node (ref "RN2") (pin "2") (pinfunction "2_2") (pintype "passive"))
    )
    (net (code "115") (name "Net-(RN4B-1)") (class "Default")
      (node (ref "JP13") (pin "2") (pinfunction "2_2") (pintype "passive"))
      (node (ref "JP3") (pin "2") (pinfunction "2_2") (pintype "passive"))
      (node (ref "R43") (pin "2") (pinfunction "2_2") (pintype "passive"))
      (node (ref "R54") (pin "2") (pinfunction "2_2") (pintype "passive"))
      (node (ref "RN4") (pin "2") (pinfunction "1_2") (pintype "passive"))
      (node (ref "RN5") (pin "8") (pinfunction "8_8") (pintype "passive"))
    )
    (net (code "116") (name "Net-(RN4C-1)") (class "Default")
      (node (ref "JP13") (pin "3") (pinfunction "3_3") (pintype "passive"))
      (node (ref "JP3") (pin "3") (pinfunction "3_3") (pintype "passive"))
      (node (ref "R42") (pin "2") (pinfunction "2_2") (pintype "passive"))
      (node (ref "R55") (pin "2") (pinfunction "2_2") (pintype "passive"))
      (node (ref "RN4") (pin "3") (pinfunction "1_3") (pintype "passive"))
      (node (ref "RN5") (pin "7") (pinfunction "7_7") (pintype "passive"))
    )
    (net (code "117") (name "Net-(RN4D-1)") (class "Default")
      (node (ref "JP13") (pin "4") (pinfunction "4_4") (pintype "passive"))
      (node (ref "JP3") (pin "4") (pinfunction "4_4") (pintype "passive"))
      (node (ref "R41") (pin "2") (pinfunction "2_2") (pintype "passive"))
      (node (ref "R56") (pin "2") (pinfunction "2_2") (pintype "passive"))
      (node (ref "RN4") (pin "4") (pinfunction "1_4") (pintype "passive"))
      (node (ref "RN5") (pin "6") (pinfunction "6_6") (pintype "passive"))
    )
    (net (code "118") (name "Net-(RN4E-1)") (class "Default")
      (node (ref "JP13") (pin "7") (pinfunction "7_7") (pintype "passive"))
      (node (ref "JP3") (pin "5") (pinfunction "5_5") (pintype "passive"))
      (node (ref "R39") (pin "2") (pinfunction "2_2") (pintype "passive"))
      (node (ref "R57") (pin "2") (pinfunction "2_2") (pintype "passive"))
      (node (ref "RN4") (pin "5") (pinfunction "1_5") (pintype "passive"))
      (node (ref "RN5") (pin "5") (pinfunction "5_5") (pintype "passive"))
    )
    (net (code "119") (name "Net-(RN4F-1)") (class "Default")
      (node (ref "JP13") (pin "8") (pinfunction "8_8") (pintype "passive"))
      (node (ref "JP3") (pin "6") (pinfunction "6_6") (pintype "passive"))
      (node (ref "R38") (pin "2") (pinfunction "2_2") (pintype "passive"))
      (node (ref "R58") (pin "2") (pinfunction "2_2") (pintype "passive"))
      (node (ref "RN4") (pin "6") (pinfunction "1_6") (pintype "passive"))
      (node (ref "RN5") (pin "4") (pinfunction "4_4") (pintype "passive"))
    )
    (net (code "120") (name "Net-(RN4G-1)") (class "Default")
      (node (ref "JP13") (pin "9") (pinfunction "9_9") (pintype "passive"))
      (node (ref "JP3") (pin "7") (pinfunction "7_7") (pintype "passive"))
      (node (ref "R37") (pin "2") (pinfunction "2_2") (pintype "passive"))
      (node (ref "R59") (pin "2") (pinfunction "2_2") (pintype "passive"))
      (node (ref "RN4") (pin "7") (pinfunction "1_7") (pintype "passive"))
      (node (ref "RN5") (pin "3") (pinfunction "3_3") (pintype "passive"))
    )
    (net (code "121") (name "Net-(RN4H-1)") (class "Default")
      (node (ref "JP13") (pin "10") (pinfunction "10_10") (pintype "passive"))
      (node (ref "JP3") (pin "8") (pinfunction "8_8") (pintype "passive"))
      (node (ref "R36") (pin "2") (pinfunction "2_2") (pintype "passive"))
      (node (ref "R60") (pin "2") (pinfunction "2_2") (pintype "passive"))
      (node (ref "RN4") (pin "8") (pinfunction "1_8") (pintype "passive"))
      (node (ref "RN5") (pin "2") (pinfunction "2_2") (pintype "passive"))
    )
    (net (code "122") (name "Net-(SJ13-1)") (class "Default")
      (node (ref "SJ13") (pin "P$1") (pinfunction "1_P$1") (pintype "passive"))
      (node (ref "U$1") (pin "PB14") (pinfunction "PB14_PB14") (pintype "bidirectional"))
    )
    (net (code "123") (name "Net-(SJ14-1)") (class "Default")
      (node (ref "SJ14") (pin "P$1") (pinfunction "1_P$1") (pintype "passive"))
      (node (ref "U$1") (pin "VIN2") (pinfunction "VIN2_VIN2") (pintype "power_in"))
    )
    (net (code "124") (name "Net-(SJ16-2)") (class "Default")
      (node (ref "JP9") (pin "2") (pinfunction "2_2") (pintype "passive"))
      (node (ref "SJ15") (pin "2") (pinfunction "2_2") (pintype "passive"))
      (node (ref "SJ16") (pin "P$2") (pinfunction "2_P$2") (pintype "passive"))
    )
    (net (code "125") (name "Net-(SJ18-2)") (class "Default")
      (node (ref "SJ18") (pin "P$2") (pinfunction "2_P$2") (pintype "passive"))
      (node (ref "U7") (pin "5") (pinfunction "VREF_5") (pintype "output"))
      (node (ref "U7B") (pin "5") (pinfunction "VREF_5") (pintype "bidirectional"))
    )
    (net (code "126") (name "Net-(U7-RS)") (class "Default")
      (node (ref "R61") (pin "1") (pinfunction "1_1") (pintype "passive"))
      (node (ref "U7") (pin "8") (pinfunction "RS_8") (pintype "input"))
      (node (ref "U7B") (pin "8") (pinfunction "RS_8") (pintype "bidirectional"))
    )
    (net (code "127") (name "Net-(U8-VOUT)") (class "Default")
      (node (ref "D1") (pin "C") (pinfunction "C_C") (pintype "passive"))
      (node (ref "L1") (pin "2") (pinfunction "2_2") (pintype "passive"))
      (node (ref "U8") (pin "2") (pinfunction "VOUT_2") (pintype "bidirectional"))
      (node (ref "U8B") (pin "7") (pinfunction "OUT_7") (pintype "passive"))
    )
    (net (code "128") (name "OLAT") (class "Default")
      (node (ref "IC3") (pin "12") (pinfunction "RCK_12") (pintype "input"))
      (node (ref "IC5") (pin "12") (pinfunction "RCK_12") (pintype "input"))
      (node (ref "R21") (pin "1") (pinfunction "1_1") (pintype "passive"))
      (node (ref "U$1") (pin "PA8") (pinfunction "PA8_PA8") (pintype "bidirectional"))
    )
    (net (code "129") (name "SCK") (class "Default")
      (node (ref "IC3") (pin "11") (pinfunction "SCK_11") (pintype "input"))
      (node (ref "IC5") (pin "11") (pinfunction "SCK_11") (pintype "input"))
      (node (ref "JP9") (pin "3") (pinfunction "3_3") (pintype "passive"))
      (node (ref "R19") (pin "1") (pinfunction "1_1") (pintype "passive"))
      (node (ref "U$1") (pin "PB3") (pinfunction "PB3_PB3") (pintype "bidirectional"))
    )
    (net (code "130") (name "SCK2") (class "Default")
      (node (ref "IC1") (pin "7") (pinfunction "CLK_7") (pintype "input"))
      (node (ref "IC4") (pin "7") (pinfunction "CLK_7") (pintype "input"))
      (node (ref "U$1") (pin "PB10") (pinfunction "PB10_PB10") (pintype "bidirectional"))
    )
    (net (code "131") (name "SLNK1") (class "Default")
      (node (ref "IC3") (pin "14") (pinfunction "SER_14") (pintype "input"))
      (node (ref "IC5") (pin "9") (pinfunction "QH*_9") (pintype "tri_state"))
      (node (ref "SJ17") (pin "P$1") (pinfunction "1_P$1") (pintype "passive"))
    )
    (net (code "132") (name "SLNK2") (class "Default")
      (node (ref "IC3") (pin "9") (pinfunction "QH*_9") (pintype "tri_state"))
      (node (ref "SJ16") (pin "P$1") (pinfunction "1_P$1") (pintype "passive"))
    )
    (net (code "133") (name "SLNK3") (class "Default")
      (node (ref "IC1") (pin "13") (pinfunction "QH_13") (pintype "output"))
      (node (ref "IC4") (pin "1") (pinfunction "SER_1") (pintype "input"))
    )
    (net (code "134") (name "SRV1") (class "Default")
      (node (ref "JP7") (pin "2") (pinfunction "2_2") (pintype "passive"))
      (node (ref "R25") (pin "2") (pinfunction "2_2") (pintype "passive"))
      (node (ref "U$1") (pin "PC9") (pinfunction "PC9_PC9") (pintype "bidirectional"))
    )
    (net (code "135") (name "SRV2") (class "Default")
      (node (ref "JP7") (pin "1") (pinfunction "1_1") (pintype "passive"))
      (node (ref "R24") (pin "2") (pinfunction "2_2") (pintype "passive"))
      (node (ref "U$1") (pin "PC7") (pinfunction "PC7_PC7") (pintype "bidirectional"))
    )
    (net (code "136") (name "SRV3") (class "Default")
      (node (ref "JP11") (pin "2") (pinfunction "2_2") (pintype "passive"))
      (node (ref "R26") (pin "2") (pinfunction "2_2") (pintype "passive"))
      (node (ref "U$1") (pin "PC8") (pinfunction "PC8_PC8") (pintype "bidirectional"))
    )
    (net (code "137") (name "SRV4") (class "Default")
      (node (ref "JP11") (pin "1") (pinfunction "1_1") (pintype "passive"))
      (node (ref "R27") (pin "2") (pinfunction "2_2") (pintype "passive"))
      (node (ref "U$1") (pin "PC6") (pinfunction "PC6_PC6") (pintype "bidirectional"))
    )
    (net (code "138") (name "SRV5") (class "Default")
      (node (ref "JP12") (pin "2") (pinfunction "2_2") (pintype "passive"))
      (node (ref "R64") (pin "2") (pinfunction "2_2") (pintype "passive"))
      (node (ref "U$1") (pin "PF1-PH1") (pinfunction "PF1-PH1_PF1-PH1") (pintype "bidirectional"))
    )
    (net (code "139") (name "SRV6") (class "Default")
      (node (ref "JP12") (pin "1") (pinfunction "1_1") (pintype "passive"))
      (node (ref "R65") (pin "2") (pinfunction "2_2") (pintype "passive"))
      (node (ref "U$1") (pin "PA15") (pinfunction "PA15_PA15") (pintype "bidirectional"))
    )
    (net (code "140") (name "SRV7") (class "Default")
      (node (ref "JP16") (pin "2") (pinfunction "2_2") (pintype "passive"))
      (node (ref "R66") (pin "2") (pinfunction "2_2") (pintype "passive"))
      (node (ref "U$1") (pin "PC12") (pinfunction "PC12_PC12") (pintype "bidirectional"))
    )
    (net (code "141") (name "SRV8") (class "Default")
      (node (ref "JP16") (pin "1") (pinfunction "1_1") (pintype "passive"))
      (node (ref "R67") (pin "2") (pinfunction "2_2") (pintype "passive"))
      (node (ref "U$1") (pin "PD2") (pinfunction "PD2_PD2") (pintype "bidirectional"))
    )
    (net (code "142") (name "TIN1") (class "Default")
      (node (ref "IC9") (pin "3") (pinfunction "+IN_3") (pintype "input"))
      (node (ref "U$1") (pin "PB2") (pinfunction "PB2_PB2") (pintype "bidirectional"))
      (node (ref "U$3") (pin "4") (pinfunction "I_4") (pintype "input"))
    )
    (net (code "143") (name "TIN2") (class "Default")
      (node (ref "IC9") (pin "5") (pinfunction "+IN_5") (pintype "input"))
      (node (ref "U$1") (pin "PB1") (pinfunction "PB1_PB1") (pintype "bidirectional"))
      (node (ref "U$2") (pin "2") (pinfunction "I_2") (pintype "input"))
    )
    (net (code "144") (name "TIN3") (class "Default")
      (node (ref "IC9") (pin "10") (pinfunction "+IN_10") (pintype "input"))
      (node (ref "U$1") (pin "PB15") (pinfunction "PB15_PB15") (pintype "bidirectional"))
      (node (ref "U$2") (pin "4") (pinfunction "I_4") (pintype "input"))
    )
    (net (code "145") (name "TIN4") (class "Default")
      (node (ref "IC9") (pin "12") (pinfunction "+IN_12") (pintype "input"))
      (node (ref "U$1") (pin "PB12") (pinfunction "PB12_PB12") (pintype "bidirectional"))
      (node (ref "U$3") (pin "2") (pinfunction "I_2") (pintype "input"))
    )
    (net (code "146") (name "TIN5") (class "Default")
      (node (ref "IC6") (pin "3") (pinfunction "+IN_3") (pintype "input"))
      (node (ref "U$1") (pin "PA4") (pinfunction "PA4_PA4") (pintype "bidirectional"))
      (node (ref "U$5") (pin "4") (pinfunction "I_4") (pintype "input"))
    )
    (net (code "147") (name "TIN6") (class "Default")
      (node (ref "IC6") (pin "5") (pinfunction "+IN_5") (pintype "input"))
      (node (ref "U$1") (pin "PC0") (pinfunction "PC0_PC0") (pintype "bidirectional"))
      (node (ref "U$4") (pin "2") (pinfunction "I_2") (pintype "input"))
    )
    (net (code "148") (name "TIN7") (class "Default")
      (node (ref "IC6") (pin "10") (pinfunction "+IN_10") (pintype "input"))
      (node (ref "U$1") (pin "PC3") (pinfunction "PC3_PC3") (pintype "bidirectional"))
      (node (ref "U$4") (pin "4") (pinfunction "I_4") (pintype "input"))
    )
    (net (code "149") (name "TIN8") (class "Default")
      (node (ref "IC6") (pin "12") (pinfunction "+IN_12") (pintype "input"))
      (node (ref "U$1") (pin "PA0") (pinfunction "PA0_PA0") (pintype "bidirectional"))
      (node (ref "U$5") (pin "2") (pinfunction "I_2") (pintype "input"))
    )
    (net (code "150") (name "V+") (class "Default")
      (node (ref "C1") (pin "1") (pinfunction "1_1") (pintype "passive"))
      (node (ref "C2") (pin "+") (pinfunction "+_+") (pintype "passive"))
      (node (ref "L1") (pin "1") (pinfunction "1_1") (pintype "passive"))
      (node (ref "U$1") (pin "E5V") (pinfunction "E5V_E5V") (pintype "power_in"))
      (node (ref "U8") (pin "3") (pinfunction "FB_3") (pintype "bidirectional"))
      (node (ref "U8B") (pin "1") (pinfunction "FB_1") (pintype "input"))
    )
    (net (code "151") (name "unconnected-(H1-MOUNT-PadB3,3)") (class "Default")
      (node (ref "H1") (pin "B3,3") (pinfunction "MOUNT_B3,3") (pintype "passive"))
    )
    (net (code "152") (name "unconnected-(H2-MOUNT-PadB3,3)") (class "Default")
      (node (ref "H2") (pin "B3,3") (pinfunction "MOUNT_B3,3") (pintype "passive"))
    )
    (net (code "153") (name "unconnected-(H3-MOUNT-PadB3,3)") (class "Default")
      (node (ref "H3") (pin "B3,3") (pinfunction "MOUNT_B3,3") (pintype "passive"))
    )
    (net (code "154") (name "unconnected-(H4-MOUNT-PadB3,3)") (class "Default")
      (node (ref "H4") (pin "B3,3") (pinfunction "MOUNT_B3,3") (pintype "passive"))
    )
    (net (code "155") (name "unconnected-(U$1-PadBOOT0)") (class "Default")
      (node (ref "U$1") (pin "BOOT0") (pinfunction "BOOT0_BOOT0") (pintype "bidirectional"))
    )
    (net (code "156") (name "unconnected-(U$1-PadIOREF2)") (class "Default")
      (node (ref "U$1") (pin "IOREF2") (pinfunction "IOREF2_IOREF2") (pintype "input"))
    )
    (net (code "157") (name "unconnected-(U$1-PadNC1-PF7)") (class "Default")
      (node (ref "U$1") (pin "NC1-PF7") (pinfunction "NC1-PF7_NC1-PF7") (pintype "bidirectional"))
    )
    (net (code "158") (name "unconnected-(U$1-PadNC2-PF6)") (class "Default")
      (node (ref "U$1") (pin "NC2-PF6") (pinfunction "NC2-PF6_NC2-PF6") (pintype "bidirectional"))
    )
    (net (code "159") (name "unconnected-(U$1-PadNC3)") (class "Default")
      (node (ref "U$1") (pin "NC3") (pinfunction "NC3_NC3") (pintype "no_connect"))
    )
    (net (code "160") (name "unconnected-(U$1-PadNC4)") (class "Default")
      (node (ref "U$1") (pin "NC4") (pinfunction "NC4_NC4") (pintype "no_connect"))
    )
    (net (code "161") (name "unconnected-(U$1-PadNC5-PD8)") (class "Default")
      (node (ref "U$1") (pin "NC5-PD8") (pinfunction "NC5-PD8_NC5-PD8") (pintype "bidirectional"))
    )
    (net (code "162") (name "unconnected-(U$1-PadNC6-PB11)") (class "Default")
      (node (ref "U$1") (pin "NC6-PB11") (pinfunction "NC6-PB11_NC6-PB11") (pintype "no_connect"))
    )
    (net (code "163") (name "unconnected-(U$1-PadNC7-PF5)") (class "Default")
      (node (ref "U$1") (pin "NC7-PF5") (pinfunction "NC7-PF5_NC7-PF5") (pintype "bidirectional"))
    )
    (net (code "164") (name "unconnected-(U$1-PadNC8-PF4)") (class "Default")
      (node (ref "U$1") (pin "NC8-PF4") (pinfunction "NC8-PF4_NC8-PF4") (pintype "bidirectional"))
    )
    (net (code "165") (name "unconnected-(U$1-PadNRESET)") (class "Default")
      (node (ref "U$1") (pin "NRESET") (pinfunction "NRESET_NRESET") (pintype "input"))
    )
    (net (code "166") (name "unconnected-(U$1-PadPA1)") (class "Default")
      (node (ref "U$1") (pin "PA1") (pinfunction "PA1_PA1") (pintype "bidirectional"))
    )
    (net (code "167") (name "unconnected-(U$1-PadPA2)") (class "Default")
      (node (ref "U$1") (pin "PA2") (pinfunction "PA2_PA2") (pintype "bidirectional"))
    )
    (net (code "168") (name "unconnected-(U$1-PadPA3)") (class "Default")
      (node (ref "U$1") (pin "PA3") (pinfunction "PA3_PA3") (pintype "bidirectional"))
    )
    (net (code "169") (name "unconnected-(U$1-PadPA5)") (class "Default")
      (node (ref "U$1") (pin "PA5") (pinfunction "PA5_PA5") (pintype "bidirectional"))
    )
    (net (code "170") (name "unconnected-(U$1-PadPA7)") (class "Default")
      (node (ref "U$1") (pin "PA7") (pinfunction "PA7_PA7") (pintype "bidirectional"))
    )
    (net (code "171") (name "unconnected-(U$1-PadPA9)") (class "Default")
      (node (ref "U$1") (pin "PA9") (pinfunction "PA9_PA9") (pintype "bidirectional"))
    )
    (net (code "172") (name "unconnected-(U$1-PadPA10)") (class "Default")
      (node (ref "U$1") (pin "PA10") (pinfunction "PA10_PA10") (pintype "bidirectional"))
    )
    (net (code "173") (name "unconnected-(U$1-PadPA11)") (class "Default")
      (node (ref "U$1") (pin "PA11") (pinfunction "PA11_PA11") (pintype "bidirectional"))
    )
    (net (code "174") (name "unconnected-(U$1-PadPA12)") (class "Default")
      (node (ref "U$1") (pin "PA12") (pinfunction "PA12_PA12") (pintype "bidirectional"))
    )
    (net (code "175") (name "unconnected-(U$1-PadPA13)") (class "Default")
      (node (ref "U$1") (pin "PA13") (pinfunction "PA13_PA13") (pintype "bidirectional"))
    )
    (net (code "176") (name "unconnected-(U$1-PadPA14)") (class "Default")
      (node (ref "U$1") (pin "PA14") (pinfunction "PA14_PA14") (pintype "bidirectional"))
    )
    (net (code "177") (name "unconnected-(U$1-PadPB0)") (class "Default")
      (node (ref "U$1") (pin "PB0") (pinfunction "PB0_PB0") (pintype "bidirectional"))
    )
    (net (code "178") (name "unconnected-(U$1-PadPB13)") (class "Default")
      (node (ref "U$1") (pin "PB13") (pinfunction "PB13_PB13") (pintype "bidirectional"))
    )
    (net (code "179") (name "unconnected-(U$1-PadPC1)") (class "Default")
      (node (ref "U$1") (pin "PC1") (pinfunction "PC1_PC1") (pintype "bidirectional"))
    )
    (net (code "180") (name "unconnected-(U$1-PadPC4)") (class "Default")
      (node (ref "U$1") (pin "PC4") (pinfunction "PC4_PC4") (pintype "bidirectional"))
    )
    (net (code "181") (name "unconnected-(U$1-PadPC5)") (class "Default")
      (node (ref "U$1") (pin "PC5") (pinfunction "PC5_PC5") (pintype "bidirectional"))
    )
    (net (code "182") (name "unconnected-(U$1-PadPC13)") (class "Default")
      (node (ref "U$1") (pin "PC13") (pinfunction "PC13_PC13") (pintype "bidirectional"))
    )
    (net (code "183") (name "unconnected-(U$1-PadPC14)") (class "Default")
      (node (ref "U$1") (pin "PC14") (pinfunction "PC14_PC14") (pintype "bidirectional"))
    )
    (net (code "184") (name "unconnected-(U$1-PadPC15)") (class "Default")
      (node (ref "U$1") (pin "PC15") (pinfunction "PC15_PC15") (pintype "bidirectional"))
    )
    (net (code "185") (name "unconnected-(U$1-PadPF0-PH0)") (class "Default")
      (node (ref "U$1") (pin "PF0-PH0") (pinfunction "PF0-PH0_PF0-PH0") (pintype "bidirectional"))
    )
  )
)
